# Schematic.net
KiCad netlist of a schematic drawn in Altium Designer
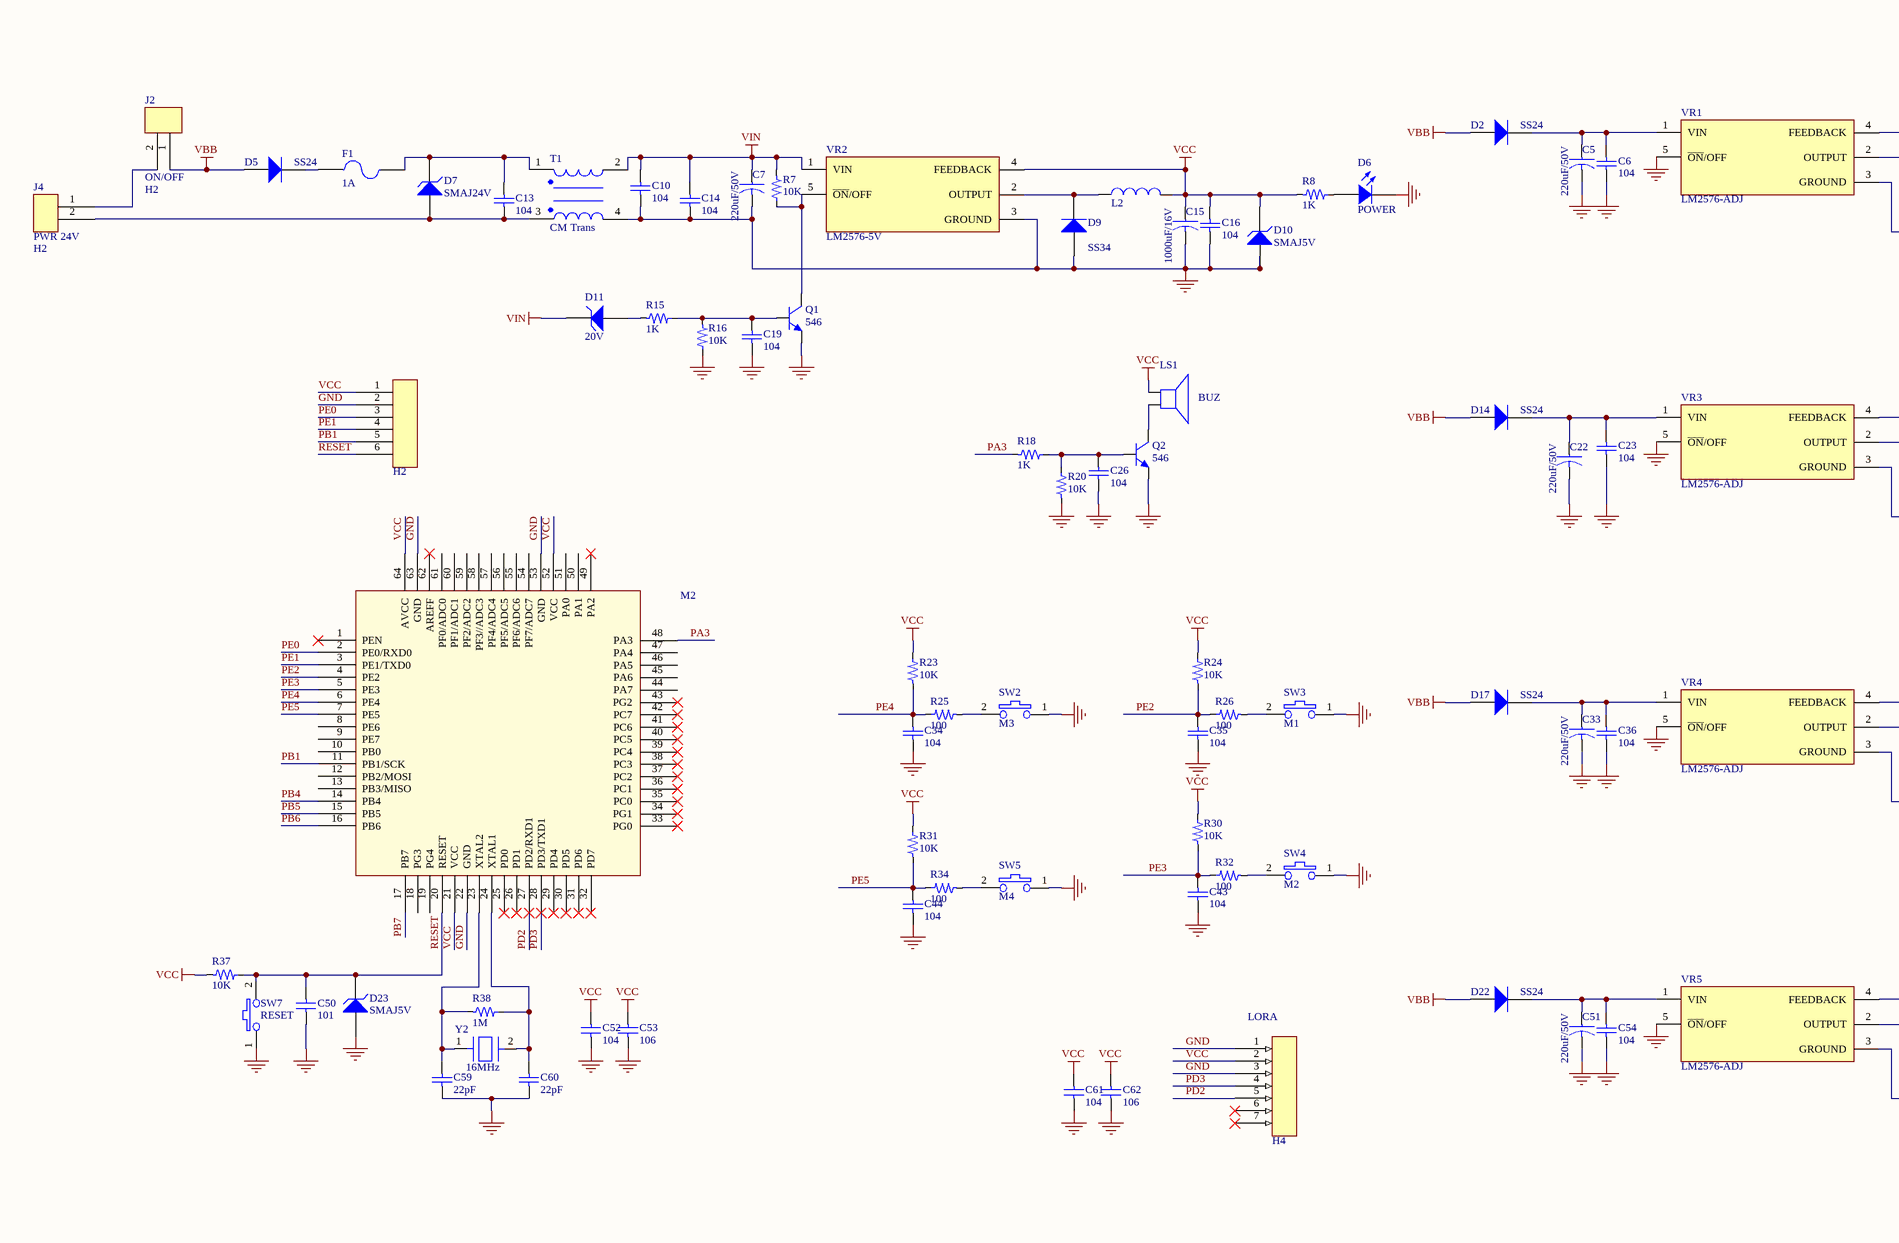
[diagram p0: Schematic.SchDoc, left]
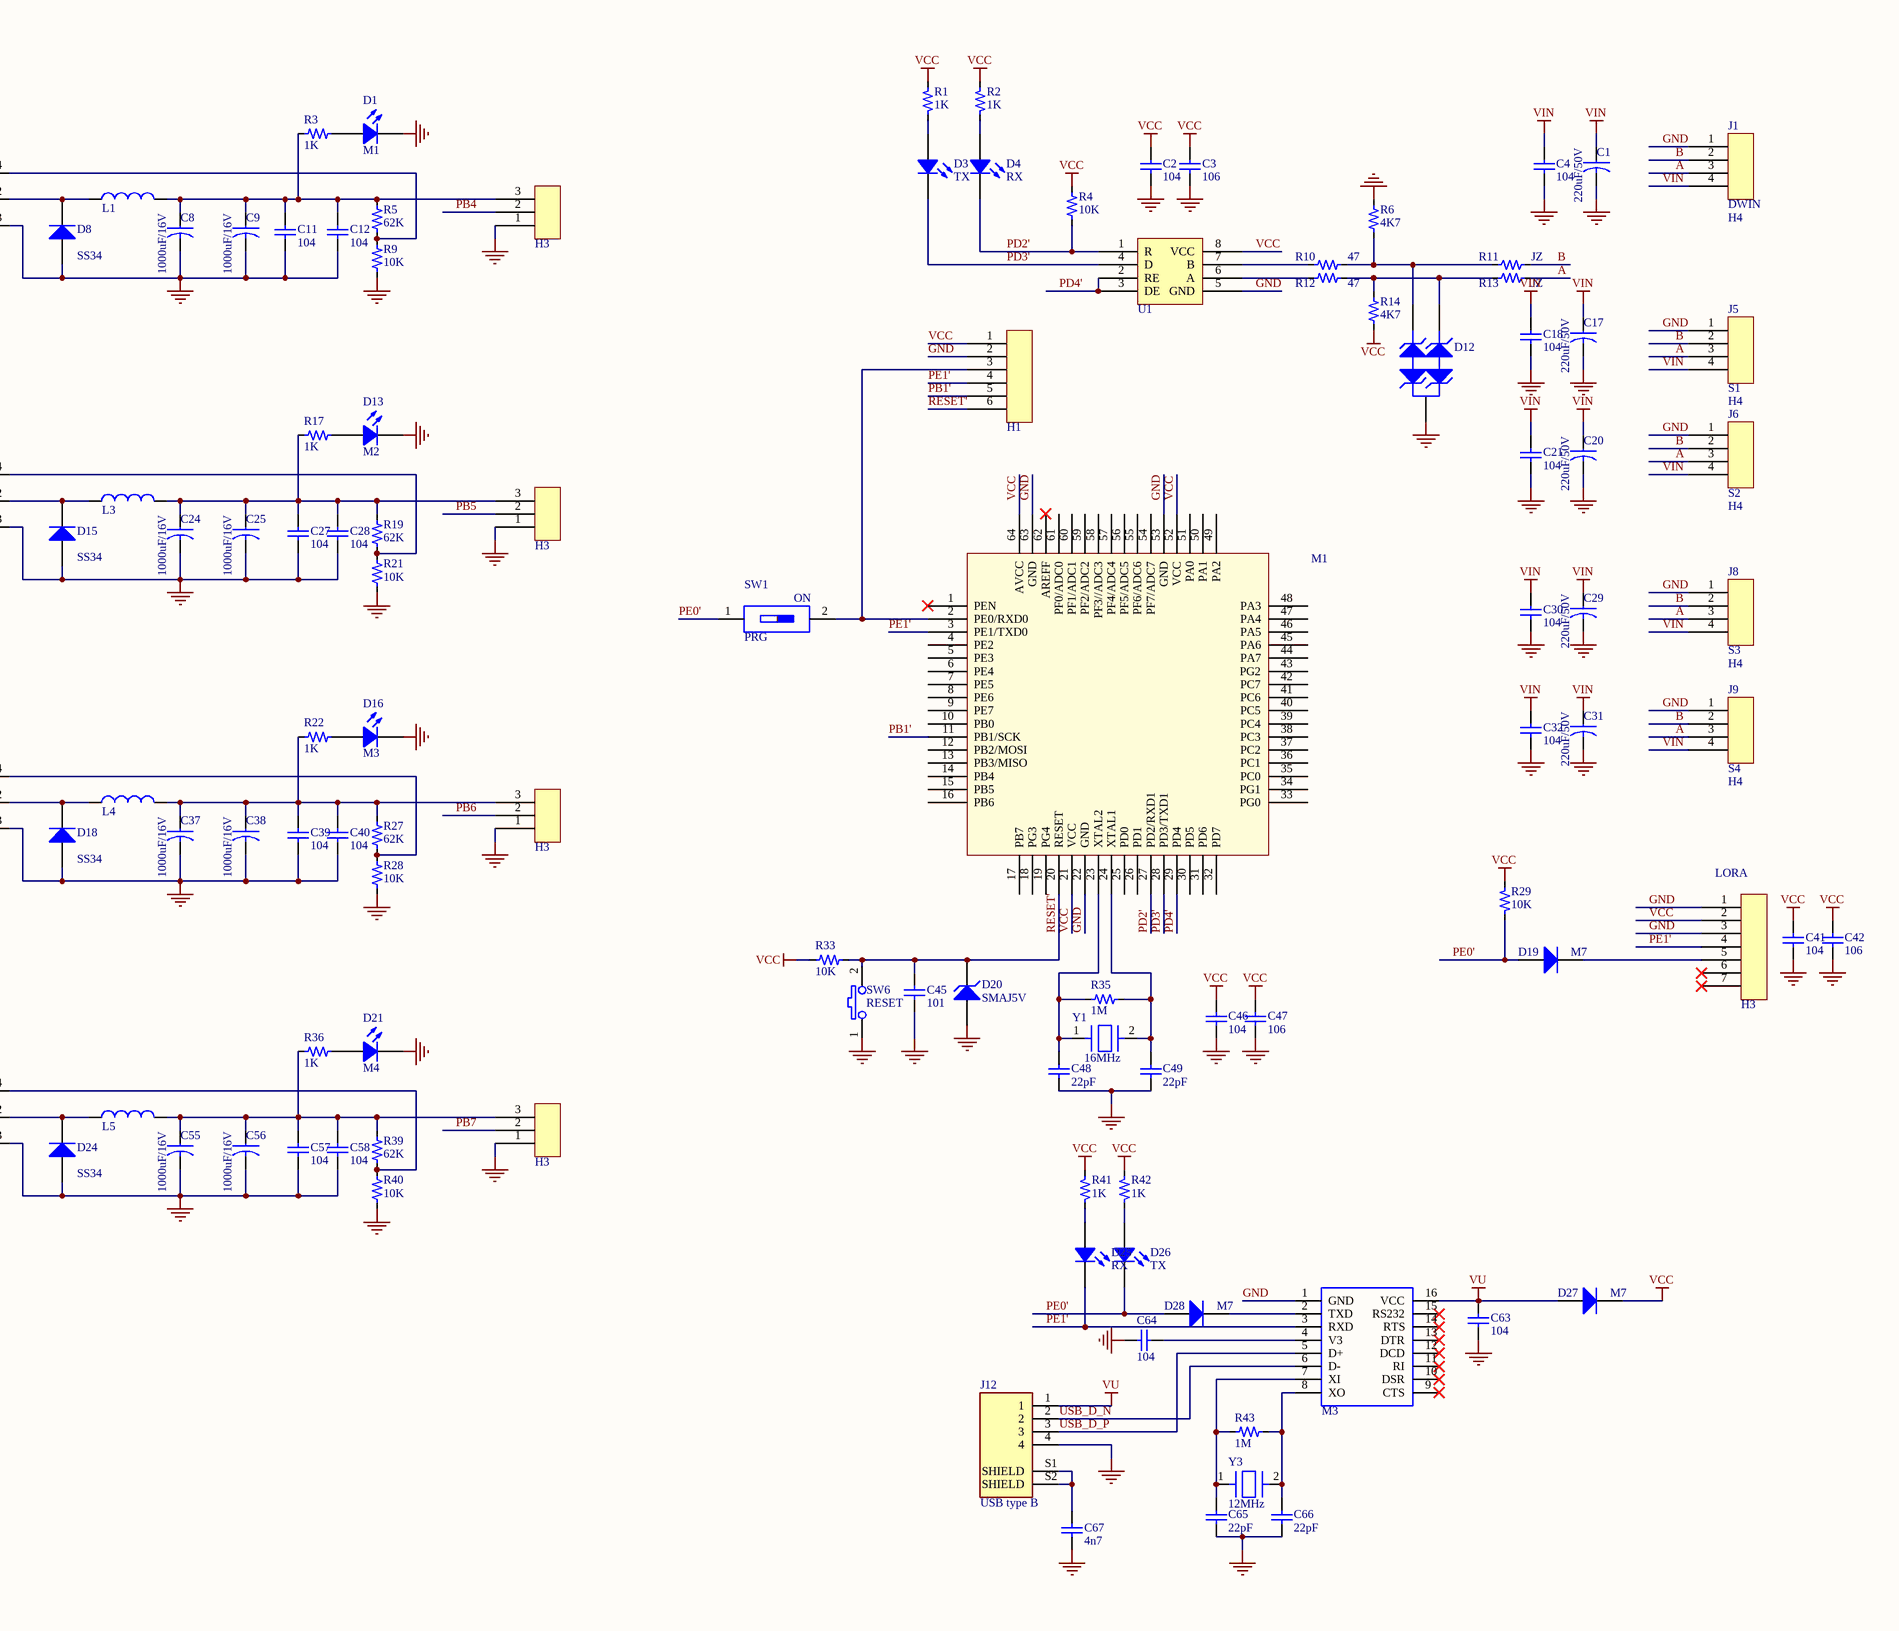
[diagram p1: Schematic.SchDoc, right]

(export (version "E")
  (design (tool "Eeschema 10.0.6"))
  (components
    (comp (ref "C1")
      (value "220uF/50V")
      (footprint "CAP-P-1W")
      (fields
        (field (name "MP") "EEE-FK1H221GP")
        (field (name "MF") "Panasonic Electronic")
        (field (name "Comment") "CAP POL")
      )
      (libsource (lib "Discrete") (part "CAP POL"))
    )
    (comp (ref "C2")
      (value "104")
      (footprint "C-1206")
      (description "Capacitor")
      (fields (field (name "Comment") "Cap") (field (name "PUBLISHER") "Altium Limited"))
      (libsource (lib "Discrete") (part "Cap"))
    )
    (comp (ref "C3")
      (value "106")
      (footprint "C-1206")
      (description "Capacitor")
      (fields (field (name "Comment") "Cap") (field (name "PUBLISHER") "Altium Limited"))
      (libsource (lib "Discrete") (part "Cap"))
    )
    (comp (ref "C4")
      (value "104")
      (footprint "C-1206")
      (description "Capacitor")
      (fields (field (name "Comment") "Cap") (field (name "PUBLISHER") "Altium Limited"))
      (libsource (lib "Discrete") (part "Cap"))
    )
    (comp (ref "C5")
      (value "220uF/50V")
      (footprint "CAP-P-1W")
      (fields
        (field (name "MP") "EEE-FK1H221GP")
        (field (name "MF") "Panasonic Electronic")
        (field (name "Comment") "CAP POL")
      )
      (libsource (lib "Discrete") (part "CAP POL"))
    )
    (comp (ref "C6")
      (value "104")
      (footprint "C-1206")
      (description "Capacitor")
      (fields (field (name "Comment") "Cap") (field (name "PUBLISHER") "Altium Limited"))
      (libsource (lib "Discrete") (part "Cap"))
    )
    (comp (ref "C7")
      (value "220uF/50V")
      (footprint "CAP-P-1W")
      (fields
        (field (name "MP") "EEE-FK1H221GP")
        (field (name "MF") "Panasonic Electronic")
        (field (name "Comment") "CAP POL")
      )
      (libsource (lib "Discrete") (part "CAP POL"))
    )
    (comp (ref "C8")
      (value "1000uF/16V")
      (footprint "CAP-P-2")
      (fields
        (field (name "MP") "EEE-FK1H221GP")
        (field (name "MF") "Panasonic Electronic")
        (field (name "Comment") "CAP POL")
      )
      (libsource (lib "Discrete") (part "CAP POL"))
    )
    (comp (ref "C9")
      (value "1000uF/16V")
      (footprint "CAP-P-2")
      (fields
        (field (name "MP") "EEE-FK1H221GP")
        (field (name "MF") "Panasonic Electronic")
        (field (name "Comment") "CAP POL")
      )
      (libsource (lib "Discrete") (part "CAP POL"))
    )
    (comp (ref "C10")
      (value "104")
      (footprint "CAP-NP-1")
      (description "Capacitor")
      (fields (field (name "Comment") "Cap") (field (name "PUBLISHER") "Altium Limited"))
      (libsource (lib "Discrete") (part "Cap"))
    )
    (comp (ref "C11")
      (value "104")
      (footprint "C-1206")
      (description "Capacitor")
      (fields (field (name "Comment") "Cap") (field (name "PUBLISHER") "Altium Limited"))
      (libsource (lib "Discrete") (part "Cap"))
    )
    (comp (ref "C12")
      (value "104")
      (footprint "C-1206")
      (description "Capacitor")
      (fields (field (name "Comment") "Cap") (field (name "PUBLISHER") "Altium Limited"))
      (libsource (lib "Discrete") (part "Cap"))
    )
    (comp (ref "C13")
      (value "104")
      (footprint "CAP-NP-1")
      (description "Capacitor")
      (fields (field (name "Comment") "Cap") (field (name "PUBLISHER") "Altium Limited"))
      (libsource (lib "Discrete") (part "Cap"))
    )
    (comp (ref "C14")
      (value "104")
      (footprint "C-1206")
      (description "Capacitor")
      (fields (field (name "Comment") "Cap") (field (name "PUBLISHER") "Altium Limited"))
      (libsource (lib "Discrete") (part "Cap"))
    )
    (comp (ref "C15")
      (value "1000uF/16V")
      (footprint "CAP-P-2")
      (fields
        (field (name "MP") "EEE-FK1H221GP")
        (field (name "MF") "Panasonic Electronic")
        (field (name "Comment") "CAP POL")
      )
      (libsource (lib "Discrete") (part "CAP POL"))
    )
    (comp (ref "C16")
      (value "104")
      (footprint "C-1206")
      (description "Capacitor")
      (fields (field (name "Comment") "Cap") (field (name "PUBLISHER") "Altium Limited"))
      (libsource (lib "Discrete") (part "Cap"))
    )
    (comp (ref "C17")
      (value "220uF/50V")
      (footprint "CAP-P-1W")
      (fields
        (field (name "MP") "EEE-FK1H221GP")
        (field (name "MF") "Panasonic Electronic")
        (field (name "Comment") "CAP POL")
      )
      (libsource (lib "Discrete") (part "CAP POL"))
    )
    (comp (ref "C18")
      (value "104")
      (footprint "C-1206")
      (description "Capacitor")
      (fields (field (name "Comment") "Cap") (field (name "PUBLISHER") "Altium Limited"))
      (libsource (lib "Discrete") (part "Cap"))
    )
    (comp (ref "C19")
      (value "104")
      (footprint "C-1206")
      (description "Capacitor")
      (fields (field (name "Comment") "Cap") (field (name "PUBLISHER") "Altium Limited"))
      (libsource (lib "Discrete") (part "Cap"))
    )
    (comp (ref "C20")
      (value "220uF/50V")
      (footprint "CAP-P-1W")
      (fields
        (field (name "MP") "EEE-FK1H221GP")
        (field (name "MF") "Panasonic Electronic")
        (field (name "Comment") "CAP POL")
      )
      (libsource (lib "Discrete") (part "CAP POL"))
    )
    (comp (ref "C21")
      (value "104")
      (footprint "C-1206")
      (description "Capacitor")
      (fields (field (name "Comment") "Cap") (field (name "PUBLISHER") "Altium Limited"))
      (libsource (lib "Discrete") (part "Cap"))
    )
    (comp (ref "C22")
      (value "220uF/50V")
      (footprint "CAP-P-1W")
      (fields
        (field (name "MP") "EEE-FK1H221GP")
        (field (name "MF") "Panasonic Electronic")
        (field (name "Comment") "CAP POL")
      )
      (libsource (lib "Discrete") (part "CAP POL"))
    )
    (comp (ref "C23")
      (value "104")
      (footprint "C-1206")
      (description "Capacitor")
      (fields (field (name "Comment") "Cap") (field (name "PUBLISHER") "Altium Limited"))
      (libsource (lib "Discrete") (part "Cap"))
    )
    (comp (ref "C24")
      (value "1000uF/16V")
      (footprint "CAP-P-2")
      (fields
        (field (name "MP") "EEE-FK1H221GP")
        (field (name "MF") "Panasonic Electronic")
        (field (name "Comment") "CAP POL")
      )
      (libsource (lib "Discrete") (part "CAP POL"))
    )
    (comp (ref "C25")
      (value "1000uF/16V")
      (footprint "CAP-P-2")
      (fields
        (field (name "MP") "EEE-FK1H221GP")
        (field (name "MF") "Panasonic Electronic")
        (field (name "Comment") "CAP POL")
      )
      (libsource (lib "Discrete") (part "CAP POL"))
    )
    (comp (ref "C26")
      (value "104")
      (footprint "C-1206")
      (description "Capacitor")
      (fields (field (name "Comment") "Cap") (field (name "PUBLISHER") "Altium Limited"))
      (libsource (lib "Discrete") (part "Cap"))
    )
    (comp (ref "C27")
      (value "104")
      (footprint "C-1206")
      (description "Capacitor")
      (fields (field (name "Comment") "Cap") (field (name "PUBLISHER") "Altium Limited"))
      (libsource (lib "Discrete") (part "Cap"))
    )
    (comp (ref "C28")
      (value "104")
      (footprint "C-1206")
      (description "Capacitor")
      (fields (field (name "Comment") "Cap") (field (name "PUBLISHER") "Altium Limited"))
      (libsource (lib "Discrete") (part "Cap"))
    )
    (comp (ref "C29")
      (value "220uF/50V")
      (footprint "CAP-P-1W")
      (fields
        (field (name "MP") "EEE-FK1H221GP")
        (field (name "MF") "Panasonic Electronic")
        (field (name "Comment") "CAP POL")
      )
      (libsource (lib "Discrete") (part "CAP POL"))
    )
    (comp (ref "C30")
      (value "104")
      (footprint "C-1206")
      (description "Capacitor")
      (fields (field (name "Comment") "Cap") (field (name "PUBLISHER") "Altium Limited"))
      (libsource (lib "Discrete") (part "Cap"))
    )
    (comp (ref "C31")
      (value "220uF/50V")
      (footprint "CAP-P-1W")
      (fields
        (field (name "MP") "EEE-FK1H221GP")
        (field (name "MF") "Panasonic Electronic")
        (field (name "Comment") "CAP POL")
      )
      (libsource (lib "Discrete") (part "CAP POL"))
    )
    (comp (ref "C32")
      (value "104")
      (footprint "C-1206")
      (description "Capacitor")
      (fields (field (name "Comment") "Cap") (field (name "PUBLISHER") "Altium Limited"))
      (libsource (lib "Discrete") (part "Cap"))
    )
    (comp (ref "C33")
      (value "220uF/50V")
      (footprint "CAP-P-1W")
      (fields
        (field (name "MP") "EEE-FK1H221GP")
        (field (name "MF") "Panasonic Electronic")
        (field (name "Comment") "CAP POL")
      )
      (libsource (lib "Discrete") (part "CAP POL"))
    )
    (comp (ref "C34")
      (value "104")
      (footprint "C-1206")
      (description "Capacitor")
      (fields (field (name "Comment") "Cap") (field (name "PUBLISHER") "Altium Limited"))
      (libsource (lib "Discrete") (part "Cap"))
    )
    (comp (ref "C35")
      (value "104")
      (footprint "C-1206")
      (description "Capacitor")
      (fields (field (name "Comment") "Cap") (field (name "PUBLISHER") "Altium Limited"))
      (libsource (lib "Discrete") (part "Cap"))
    )
    (comp (ref "C36")
      (value "104")
      (footprint "C-1206")
      (description "Capacitor")
      (fields (field (name "Comment") "Cap") (field (name "PUBLISHER") "Altium Limited"))
      (libsource (lib "Discrete") (part "Cap"))
    )
    (comp (ref "C37")
      (value "1000uF/16V")
      (footprint "CAP-P-2")
      (fields
        (field (name "MP") "EEE-FK1H221GP")
        (field (name "MF") "Panasonic Electronic")
        (field (name "Comment") "CAP POL")
      )
      (libsource (lib "Discrete") (part "CAP POL"))
    )
    (comp (ref "C38")
      (value "1000uF/16V")
      (footprint "CAP-P-2")
      (fields
        (field (name "MP") "EEE-FK1H221GP")
        (field (name "MF") "Panasonic Electronic")
        (field (name "Comment") "CAP POL")
      )
      (libsource (lib "Discrete") (part "CAP POL"))
    )
    (comp (ref "C39")
      (value "104")
      (footprint "C-1206")
      (description "Capacitor")
      (fields (field (name "Comment") "Cap") (field (name "PUBLISHER") "Altium Limited"))
      (libsource (lib "Discrete") (part "Cap"))
    )
    (comp (ref "C40")
      (value "104")
      (footprint "C-1206")
      (description "Capacitor")
      (fields (field (name "Comment") "Cap") (field (name "PUBLISHER") "Altium Limited"))
      (libsource (lib "Discrete") (part "Cap"))
    )
    (comp (ref "C41")
      (value "104")
      (footprint "C-1206")
      (description "Capacitor")
      (fields (field (name "Comment") "Cap") (field (name "PUBLISHER") "Altium Limited"))
      (libsource (lib "Discrete") (part "Cap"))
    )
    (comp (ref "C42")
      (value "106")
      (footprint "C-1206")
      (description "Capacitor")
      (fields (field (name "Comment") "Cap") (field (name "PUBLISHER") "Altium Limited"))
      (libsource (lib "Discrete") (part "Cap"))
    )
    (comp (ref "C43")
      (value "104")
      (footprint "C-1206")
      (description "Capacitor")
      (fields (field (name "Comment") "Cap") (field (name "PUBLISHER") "Altium Limited"))
      (libsource (lib "Discrete") (part "Cap"))
    )
    (comp (ref "C44")
      (value "104")
      (footprint "C-1206")
      (description "Capacitor")
      (fields (field (name "Comment") "Cap") (field (name "PUBLISHER") "Altium Limited"))
      (libsource (lib "Discrete") (part "Cap"))
    )
    (comp (ref "C45")
      (value "101")
      (footprint "C-1206")
      (description "Capacitor")
      (fields (field (name "Comment") "Cap") (field (name "PUBLISHER") "Altium Limited"))
      (libsource (lib "Discrete") (part "Cap"))
    )
    (comp (ref "C46")
      (value "104")
      (footprint "C-1206")
      (description "Capacitor")
      (fields (field (name "Comment") "Cap") (field (name "PUBLISHER") "Altium Limited"))
      (libsource (lib "Discrete") (part "Cap"))
    )
    (comp (ref "C47")
      (value "106")
      (footprint "C-1206")
      (description "Capacitor")
      (fields (field (name "Comment") "Cap") (field (name "PUBLISHER") "Altium Limited"))
      (libsource (lib "Discrete") (part "Cap"))
    )
    (comp (ref "C48")
      (value "22pF")
      (footprint "C-1206")
      (description "Capacitor")
      (fields (field (name "Comment") "Cap") (field (name "PUBLISHER") "Altium Limited"))
      (libsource (lib "Discrete") (part "Cap"))
    )
    (comp (ref "C49")
      (value "22pF")
      (footprint "C-1206")
      (description "Capacitor")
      (fields (field (name "Comment") "Cap") (field (name "PUBLISHER") "Altium Limited"))
      (libsource (lib "Discrete") (part "Cap"))
    )
    (comp (ref "C50")
      (value "101")
      (footprint "C-1206")
      (description "Capacitor")
      (fields (field (name "Comment") "Cap") (field (name "PUBLISHER") "Altium Limited"))
      (libsource (lib "Discrete") (part "Cap"))
    )
    (comp (ref "C51")
      (value "220uF/50V")
      (footprint "CAP-P-1W")
      (fields
        (field (name "MP") "EEE-FK1H221GP")
        (field (name "MF") "Panasonic Electronic")
        (field (name "Comment") "CAP POL")
      )
      (libsource (lib "Discrete") (part "CAP POL"))
    )
    (comp (ref "C52")
      (value "104")
      (footprint "C-1206")
      (description "Capacitor")
      (fields (field (name "Comment") "Cap") (field (name "PUBLISHER") "Altium Limited"))
      (libsource (lib "Discrete") (part "Cap"))
    )
    (comp (ref "C53")
      (value "106")
      (footprint "C-1206")
      (description "Capacitor")
      (fields (field (name "Comment") "Cap") (field (name "PUBLISHER") "Altium Limited"))
      (libsource (lib "Discrete") (part "Cap"))
    )
    (comp (ref "C54")
      (value "104")
      (footprint "C-1206")
      (description "Capacitor")
      (fields (field (name "Comment") "Cap") (field (name "PUBLISHER") "Altium Limited"))
      (libsource (lib "Discrete") (part "Cap"))
    )
    (comp (ref "C55")
      (value "1000uF/16V")
      (footprint "CAP-P-2")
      (fields
        (field (name "MP") "EEE-FK1H221GP")
        (field (name "MF") "Panasonic Electronic")
        (field (name "Comment") "CAP POL")
      )
      (libsource (lib "Discrete") (part "CAP POL"))
    )
    (comp (ref "C56")
      (value "1000uF/16V")
      (footprint "CAP-P-2")
      (fields
        (field (name "MP") "EEE-FK1H221GP")
        (field (name "MF") "Panasonic Electronic")
        (field (name "Comment") "CAP POL")
      )
      (libsource (lib "Discrete") (part "CAP POL"))
    )
    (comp (ref "C57")
      (value "104")
      (footprint "C-1206")
      (description "Capacitor")
      (fields (field (name "Comment") "Cap") (field (name "PUBLISHER") "Altium Limited"))
      (libsource (lib "Discrete") (part "Cap"))
    )
    (comp (ref "C58")
      (value "104")
      (footprint "C-1206")
      (description "Capacitor")
      (fields (field (name "Comment") "Cap") (field (name "PUBLISHER") "Altium Limited"))
      (libsource (lib "Discrete") (part "Cap"))
    )
    (comp (ref "C59")
      (value "22pF")
      (footprint "C-1206")
      (description "Capacitor")
      (fields (field (name "Comment") "Cap") (field (name "PUBLISHER") "Altium Limited"))
      (libsource (lib "Discrete") (part "Cap"))
    )
    (comp (ref "C60")
      (value "22pF")
      (footprint "C-1206")
      (description "Capacitor")
      (fields (field (name "Comment") "Cap") (field (name "PUBLISHER") "Altium Limited"))
      (libsource (lib "Discrete") (part "Cap"))
    )
    (comp (ref "C61")
      (value "104")
      (footprint "C-1206")
      (description "Capacitor")
      (fields (field (name "Comment") "Cap") (field (name "PUBLISHER") "Altium Limited"))
      (libsource (lib "Discrete") (part "Cap"))
    )
    (comp (ref "C62")
      (value "106")
      (footprint "C-1206")
      (description "Capacitor")
      (fields (field (name "Comment") "Cap") (field (name "PUBLISHER") "Altium Limited"))
      (libsource (lib "Discrete") (part "Cap"))
    )
    (comp (ref "C63")
      (value "104")
      (footprint "C-1206")
      (description "Capacitor")
      (fields (field (name "Comment") "Cap") (field (name "PUBLISHER") "Altium Limited"))
      (libsource (lib "Discrete") (part "Cap"))
    )
    (comp (ref "C64")
      (value "104")
      (footprint "C-1206")
      (description "Capacitor")
      (fields (field (name "Comment") "Cap") (field (name "PUBLISHER") "Altium Limited"))
      (libsource (lib "Discrete") (part "Cap"))
    )
    (comp (ref "C65")
      (value "22pF")
      (footprint "C-1206")
      (description "Capacitor")
      (fields (field (name "Comment") "Cap") (field (name "PUBLISHER") "Altium Limited"))
      (libsource (lib "Discrete") (part "Cap"))
    )
    (comp (ref "C66")
      (value "22pF")
      (footprint "C-1206")
      (description "Capacitor")
      (fields (field (name "Comment") "Cap") (field (name "PUBLISHER") "Altium Limited"))
      (libsource (lib "Discrete") (part "Cap"))
    )
    (comp (ref "C67")
      (value "4n7")
      (footprint "C-1206")
      (description "Capacitor")
      (fields (field (name "Comment") "Cap") (field (name "PUBLISHER") "Altium Limited"))
      (libsource (lib "Discrete") (part "Cap"))
    )
    (comp (ref "D1")
      (value "M1")
      (footprint "L-1206")
      (description "Typical INFRARED GaAs LED")
      (fields (field (name "Comment") "PWR") (field (name "PUBLISHER") "Altium Limited"))
      (libsource (lib "Discrete") (part "LED"))
    )
    (comp (ref "D2")
      (value "SS24")
      (footprint "SMB")
      (description "Default Diode")
      (fields (field (name "Comment") "Diode") (field (name "PUBLISHER") "Altium Limited"))
      (libsource (lib "Discrete") (part "Diode"))
    )
    (comp (ref "D3")
      (value "TX")
      (footprint "L-1206")
      (description "Typical INFRARED GaAs LED")
      (fields (field (name "PUBLISHER") "Altium Limited"))
      (libsource (lib "Discrete") (part "LED"))
    )
    (comp (ref "D4")
      (value "RX")
      (footprint "L-1206")
      (description "Typical INFRARED GaAs LED")
      (fields (field (name "PUBLISHER") "Altium Limited"))
      (libsource (lib "Discrete") (part "LED"))
    )
    (comp (ref "D5")
      (value "SS24")
      (footprint "SMB")
      (description "Default Diode")
      (fields (field (name "Comment") "Diode") (field (name "PUBLISHER") "Altium Limited"))
      (libsource (lib "Discrete") (part "Diode"))
    )
    (comp (ref "D6")
      (value "POWER")
      (footprint "L-1206")
      (description "Typical INFRARED GaAs LED")
      (fields (field (name "Comment") "PWR") (field (name "PUBLISHER") "Altium Limited"))
      (libsource (lib "Discrete") (part "LED"))
    )
    (comp (ref "D7")
      (value "SMAJ24V")
      (footprint "SMA")
      (fields
        (field (name "MP") "SMBJ24CA")
        (field (name "MF") "Taiwan Semiconductor")
        (field (name "Comment") "Zener Diode")
      )
      (libsource (lib "Discrete") (part "Zener Diode"))
    )
    (comp (ref "D8")
      (value "SS34")
      (footprint "SMA")
      (description "Default Diode")
      (fields (field (name "Comment") "Diode") (field (name "PUBLISHER") "Altium Limited"))
      (libsource (lib "Discrete") (part "Diode"))
    )
    (comp (ref "D9")
      (value "SS34")
      (footprint "SMA")
      (description "Default Diode")
      (fields (field (name "Comment") "Diode") (field (name "PUBLISHER") "Altium Limited"))
      (libsource (lib "Discrete") (part "Diode"))
    )
    (comp (ref "D10")
      (value "SMAJ5V")
      (footprint "SMA")
      (fields
        (field (name "MP") "SMBJ24CA")
        (field (name "MF") "Taiwan Semiconductor")
        (field (name "Comment") "Zener Diode")
      )
      (libsource (lib "Discrete") (part "Zener Diode"))
    )
    (comp (ref "D11")
      (value "20V")
      (footprint "ZDiode-3")
      (fields
        (field (name "MP") "SMBJ24CA")
        (field (name "MF") "Taiwan Semiconductor")
        (field (name "Comment") "Zener Diode")
      )
      (libsource (lib "Discrete") (part "Zener Diode"))
    )
    (comp (ref "D12") (value "PSM712") (footprint "SOT23") (libsource (lib "Discrete") (part "PSM712")))
    (comp (ref "D13")
      (value "M2")
      (footprint "L-1206")
      (description "Typical INFRARED GaAs LED")
      (fields (field (name "Comment") "PWR") (field (name "PUBLISHER") "Altium Limited"))
      (libsource (lib "Discrete") (part "LED"))
    )
    (comp (ref "D14")
      (value "SS24")
      (footprint "SMB")
      (description "Default Diode")
      (fields (field (name "Comment") "Diode") (field (name "PUBLISHER") "Altium Limited"))
      (libsource (lib "Discrete") (part "Diode"))
    )
    (comp (ref "D15")
      (value "SS34")
      (footprint "SMA")
      (description "Default Diode")
      (fields (field (name "Comment") "Diode") (field (name "PUBLISHER") "Altium Limited"))
      (libsource (lib "Discrete") (part "Diode"))
    )
    (comp (ref "D16")
      (value "M3")
      (footprint "L-1206")
      (description "Typical INFRARED GaAs LED")
      (fields (field (name "Comment") "PWR") (field (name "PUBLISHER") "Altium Limited"))
      (libsource (lib "Discrete") (part "LED"))
    )
    (comp (ref "D17")
      (value "SS24")
      (footprint "SMB")
      (description "Default Diode")
      (fields (field (name "Comment") "Diode") (field (name "PUBLISHER") "Altium Limited"))
      (libsource (lib "Discrete") (part "Diode"))
    )
    (comp (ref "D18")
      (value "SS34")
      (footprint "SMA")
      (description "Default Diode")
      (fields (field (name "Comment") "Diode") (field (name "PUBLISHER") "Altium Limited"))
      (libsource (lib "Discrete") (part "Diode"))
    )
    (comp (ref "D19")
      (value "M7")
      (footprint "SMA")
      (description "Default Diode")
      (fields (field (name "Comment") "Diode") (field (name "PUBLISHER") "Altium Limited"))
      (libsource (lib "Discrete") (part "Diode"))
    )
    (comp (ref "D20")
      (value "SMAJ5V")
      (footprint "SMA")
      (fields
        (field (name "MP") "SMBJ24CA")
        (field (name "MF") "Taiwan Semiconductor")
        (field (name "Comment") "Zener Diode")
      )
      (libsource (lib "Discrete") (part "Zener Diode"))
    )
    (comp (ref "D21")
      (value "M4")
      (footprint "L-1206")
      (description "Typical INFRARED GaAs LED")
      (fields (field (name "Comment") "PWR") (field (name "PUBLISHER") "Altium Limited"))
      (libsource (lib "Discrete") (part "LED"))
    )
    (comp (ref "D22")
      (value "SS24")
      (footprint "SMB")
      (description "Default Diode")
      (fields (field (name "Comment") "Diode") (field (name "PUBLISHER") "Altium Limited"))
      (libsource (lib "Discrete") (part "Diode"))
    )
    (comp (ref "D23")
      (value "SMAJ5V")
      (footprint "SMA")
      (fields
        (field (name "MP") "SMBJ24CA")
        (field (name "MF") "Taiwan Semiconductor")
        (field (name "Comment") "Zener Diode")
      )
      (libsource (lib "Discrete") (part "Zener Diode"))
    )
    (comp (ref "D24")
      (value "SS34")
      (footprint "SMA")
      (description "Default Diode")
      (fields (field (name "Comment") "Diode") (field (name "PUBLISHER") "Altium Limited"))
      (libsource (lib "Discrete") (part "Diode"))
    )
    (comp (ref "D25")
      (value "RX")
      (footprint "L-1206")
      (description "Typical INFRARED GaAs LED")
      (fields (field (name "PUBLISHER") "Altium Limited"))
      (libsource (lib "Discrete") (part "LED"))
    )
    (comp (ref "D26")
      (value "TX")
      (footprint "L-1206")
      (description "Typical INFRARED GaAs LED")
      (fields (field (name "PUBLISHER") "Altium Limited"))
      (libsource (lib "Discrete") (part "LED"))
    )
    (comp (ref "D27")
      (value "M7")
      (footprint "SMA")
      (description "Default Diode")
      (fields (field (name "Comment") "Diode") (field (name "PUBLISHER") "Altium Limited"))
      (libsource (lib "Discrete") (part "Diode"))
    )
    (comp (ref "D28")
      (value "M7")
      (footprint "SMA")
      (description "Default Diode")
      (fields (field (name "Comment") "Diode") (field (name "PUBLISHER") "Altium Limited"))
      (libsource (lib "Discrete") (part "Diode"))
    )
    (comp (ref "F1")
      (value "1A")
      (footprint "FUSE")
      (description "Fuse")
      (fields (field (name "PUBLISHER") "Altium Limited"))
      (libsource (lib "Discrete") (part "Fuse"))
    )
    (comp (ref "H1") (value "H_1X6") (footprint "Header-01X06") (libsource (lib "Headers") (part "H_1X6")))
    (comp (ref "H2") (value "H_1X6") (footprint "Header-01X06") (libsource (lib "Headers") (part "H_1X6")))
    (comp (ref "H3") (value "LORA") (footprint "Header-01X07") (libsource (lib "Headers") (part "H_1X7")))
    (comp (ref "H4") (value "LORA") (footprint "Header-01X07") (libsource (lib "Headers") (part "H_1X7")))
    (comp (ref "J1")
      (value "DWIN")
      (footprint "STD-04-3.55MM")
      (fields (field (name "ALTIUM_VALUE") "H4"))
      (libsource (lib "Connectors") (part "CON04"))
    )
    (comp (ref "J2")
      (value "ON/OFF")
      (footprint "PLG-02-B")
      (fields (field (name "ALTIUM_VALUE") "H2"))
      (libsource (lib "Connectors") (part "CON02"))
    )
    (comp (ref "J3")
      (value "H3")
      (footprint "PLG-03-B")
      (fields (field (name "Comment") "MOTOR1"))
      (libsource (lib "Connectors") (part "CON03"))
    )
    (comp (ref "J4")
      (value "PWR 24V")
      (footprint "PLG-02-B")
      (fields (field (name "ALTIUM_VALUE") "H2"))
      (libsource (lib "") (part "CON02_1"))
    )
    (comp (ref "J5")
      (value "S1")
      (footprint "STD-04-3.55MM")
      (fields (field (name "ALTIUM_VALUE") "H4"))
      (libsource (lib "Connectors") (part "CON04"))
    )
    (comp (ref "J6")
      (value "S2")
      (footprint "STD-04-3.55MM")
      (fields (field (name "ALTIUM_VALUE") "H4"))
      (libsource (lib "Connectors") (part "CON04"))
    )
    (comp (ref "J7")
      (value "H3")
      (footprint "PLG-03-B")
      (fields (field (name "Comment") "MOTOR2"))
      (libsource (lib "Connectors") (part "CON03"))
    )
    (comp (ref "J8")
      (value "S3")
      (footprint "STD-04-3.55MM")
      (fields (field (name "ALTIUM_VALUE") "H4"))
      (libsource (lib "Connectors") (part "CON04"))
    )
    (comp (ref "J9")
      (value "S4")
      (footprint "STD-04-3.55MM")
      (fields (field (name "ALTIUM_VALUE") "H4"))
      (libsource (lib "Connectors") (part "CON04"))
    )
    (comp (ref "J10")
      (value "H3")
      (footprint "PLG-03-B")
      (fields (field (name "Comment") "MOTOR3"))
      (libsource (lib "Connectors") (part "CON03"))
    )
    (comp (ref "J11")
      (value "H3")
      (footprint "PLG-03-B")
      (fields (field (name "Comment") "MOTOR4"))
      (libsource (lib "Connectors") (part "CON03"))
    )
    (comp (ref "J12")
      (value "USB type B")
      (footprint "USB-Type-B")
      (description "USB-B (USB TYPE-B) USB 2.0 Receptacle Connector 4 Position Through Hole, Right Angle")
      (fields (field (name "MF") "Wurth Elektronik") (field (name "MP") "61400416121"))
      (libsource (lib "Sockets") (part "USB type B"))
    )
    (comp (ref "L1")
      (value "Inductor")
      (footprint "L_9X12")
      (fields (field (name "PUBLISHER") "Altium Limited"))
      (libsource (lib "Discrete") (part "Inductor"))
    )
    (comp (ref "L2")
      (value "Inductor")
      (footprint "L_9X12")
      (fields (field (name "PUBLISHER") "Altium Limited"))
      (libsource (lib "Discrete") (part "Inductor"))
    )
    (comp (ref "L3")
      (value "Inductor")
      (footprint "L_9X12")
      (fields (field (name "PUBLISHER") "Altium Limited"))
      (libsource (lib "Discrete") (part "Inductor"))
    )
    (comp (ref "L4")
      (value "Inductor")
      (footprint "L_9X12")
      (fields (field (name "PUBLISHER") "Altium Limited"))
      (libsource (lib "Discrete") (part "Inductor"))
    )
    (comp (ref "L5")
      (value "Inductor")
      (footprint "L_9X12")
      (fields (field (name "PUBLISHER") "Altium Limited"))
      (libsource (lib "Discrete") (part "Inductor"))
    )
    (comp (ref "LS1")
      (value "BUZ")
      (footprint "Buzzer")
      (fields
        (field (name "MF") "PUI Audio, Inc.")
        (field (name "MP") "AI-1027-TWT-3V-R")
        (field (name "Comment") "Buzzer")
      )
      (libsource (lib "Discrete") (part "Buzzer"))
    )
    (comp (ref "M1")
      (value "Atmega128-SMD")
      (footprint "Quad64")
      (libsource (lib "Microcontrollers") (part "Atmega128-SMD"))
    )
    (comp (ref "M2")
      (value "Atmega128-SMD")
      (footprint "Quad64")
      (libsource (lib "Microcontrollers") (part "Atmega128-SMD"))
    )
    (comp (ref "M3") (value "CH340") (footprint "SOIC-16") (libsource (lib "Misc") (part "CH340")))
    (comp (ref "Q1")
      (value "546")
      (footprint "SOT23")
      (description "NPN Bipolar Transistor")
      (fields (field (name "Comment") "NPN") (field (name "PUBLISHER") "Altium Limited"))
      (libsource (lib "Discrete") (part "NPN-CBE"))
    )
    (comp (ref "Q2")
      (value "546")
      (footprint "SOT23")
      (description "NPN Bipolar Transistor")
      (fields (field (name "Comment") "NPN") (field (name "PUBLISHER") "Altium Limited"))
      (libsource (lib "Discrete") (part "NPN-CBE"))
    )
    (comp (ref "R1")
      (value "1K")
      (footprint "R-1206")
      (description "Resistor")
      (fields (field (name "PUBLISHER") "Altium Limited"))
      (libsource (lib "Discrete") (part "Resistor"))
    )
    (comp (ref "R2")
      (value "1K")
      (footprint "R-1206")
      (description "Resistor")
      (fields (field (name "PUBLISHER") "Altium Limited"))
      (libsource (lib "Discrete") (part "Resistor"))
    )
    (comp (ref "R3")
      (value "1K")
      (footprint "R-1206")
      (description "Resistor")
      (fields (field (name "PUBLISHER") "Altium Limited"))
      (libsource (lib "") (part "Resistor_1"))
    )
    (comp (ref "R4")
      (value "10K")
      (footprint "R-1206")
      (description "Resistor")
      (fields (field (name "PUBLISHER") "Altium Limited"))
      (libsource (lib "") (part "Resistor_2"))
    )
    (comp (ref "R5")
      (value "62K")
      (footprint "R-1206")
      (description "Resistor")
      (fields (field (name "PUBLISHER") "Altium Limited"))
      (libsource (lib "") (part "Resistor_2"))
    )
    (comp (ref "R6")
      (value "4K7")
      (footprint "R-1206")
      (description "Resistor")
      (fields (field (name "PUBLISHER") "Altium Limited"))
      (libsource (lib "") (part "Resistor_2"))
    )
    (comp (ref "R7")
      (value "10K")
      (footprint "R-1206")
      (description "Resistor")
      (fields (field (name "PUBLISHER") "Altium Limited"))
      (libsource (lib "") (part "Resistor_3"))
    )
    (comp (ref "R8")
      (value "1K")
      (footprint "R-1206")
      (description "Resistor")
      (fields (field (name "PUBLISHER") "Altium Limited"))
      (libsource (lib "") (part "Resistor_1"))
    )
    (comp (ref "R9")
      (value "10K")
      (footprint "R-1206")
      (description "Resistor")
      (fields (field (name "PUBLISHER") "Altium Limited"))
      (libsource (lib "") (part "Resistor_2"))
    )
    (comp (ref "R10")
      (value "47")
      (footprint "R-1206")
      (description "Resistor")
      (fields (field (name "PUBLISHER") "Altium Limited"))
      (libsource (lib "") (part "Resistor_1"))
    )
    (comp (ref "R11")
      (value "JZ")
      (footprint "R-1206")
      (description "Resistor")
      (fields (field (name "PUBLISHER") "Altium Limited"))
      (libsource (lib "") (part "Resistor_1"))
    )
    (comp (ref "R12")
      (value "47")
      (footprint "R-1206")
      (description "Resistor")
      (fields (field (name "PUBLISHER") "Altium Limited"))
      (libsource (lib "") (part "Resistor_1"))
    )
    (comp (ref "R13")
      (value "JZ")
      (footprint "R-1206")
      (description "Resistor")
      (fields (field (name "PUBLISHER") "Altium Limited"))
      (libsource (lib "") (part "Resistor_1"))
    )
    (comp (ref "R14")
      (value "4K7")
      (footprint "R-1206")
      (description "Resistor")
      (fields (field (name "PUBLISHER") "Altium Limited"))
      (libsource (lib "") (part "Resistor_2"))
    )
    (comp (ref "R15")
      (value "1K")
      (footprint "R-1206")
      (description "Resistor")
      (fields (field (name "PUBLISHER") "Altium Limited"))
      (libsource (lib "") (part "Resistor_1"))
    )
    (comp (ref "R16")
      (value "10K")
      (footprint "R-1206")
      (description "Resistor")
      (fields (field (name "PUBLISHER") "Altium Limited"))
      (libsource (lib "") (part "Resistor_3"))
    )
    (comp (ref "R17")
      (value "1K")
      (footprint "R-1206")
      (description "Resistor")
      (fields (field (name "PUBLISHER") "Altium Limited"))
      (libsource (lib "") (part "Resistor_1"))
    )
    (comp (ref "R18")
      (value "1K")
      (footprint "R-1206")
      (description "Resistor")
      (fields (field (name "PUBLISHER") "Altium Limited"))
      (libsource (lib "") (part "Resistor_1"))
    )
    (comp (ref "R19")
      (value "62K")
      (footprint "R-1206")
      (description "Resistor")
      (fields (field (name "PUBLISHER") "Altium Limited"))
      (libsource (lib "") (part "Resistor_2"))
    )
    (comp (ref "R20")
      (value "10K")
      (footprint "R-1206")
      (description "Resistor")
      (fields (field (name "PUBLISHER") "Altium Limited"))
      (libsource (lib "") (part "Resistor_2"))
    )
    (comp (ref "R21")
      (value "10K")
      (footprint "R-1206")
      (description "Resistor")
      (fields (field (name "PUBLISHER") "Altium Limited"))
      (libsource (lib "") (part "Resistor_2"))
    )
    (comp (ref "R22")
      (value "1K")
      (footprint "R-1206")
      (description "Resistor")
      (fields (field (name "PUBLISHER") "Altium Limited"))
      (libsource (lib "") (part "Resistor_1"))
    )
    (comp (ref "R23")
      (value "10K")
      (footprint "R-1206")
      (description "Resistor")
      (fields (field (name "PUBLISHER") "Altium Limited"))
      (libsource (lib "") (part "Resistor_2"))
    )
    (comp (ref "R24")
      (value "10K")
      (footprint "R-1206")
      (description "Resistor")
      (fields (field (name "PUBLISHER") "Altium Limited"))
      (libsource (lib "") (part "Resistor_2"))
    )
    (comp (ref "R25")
      (value "100")
      (footprint "R-1206")
      (description "Resistor")
      (fields (field (name "PUBLISHER") "Altium Limited"))
      (libsource (lib "Discrete") (part "Resistor"))
    )
    (comp (ref "R26")
      (value "100")
      (footprint "R-1206")
      (description "Resistor")
      (fields (field (name "PUBLISHER") "Altium Limited"))
      (libsource (lib "Discrete") (part "Resistor"))
    )
    (comp (ref "R27")
      (value "62K")
      (footprint "R-1206")
      (description "Resistor")
      (fields (field (name "PUBLISHER") "Altium Limited"))
      (libsource (lib "") (part "Resistor_2"))
    )
    (comp (ref "R28")
      (value "10K")
      (footprint "R-1206")
      (description "Resistor")
      (fields (field (name "PUBLISHER") "Altium Limited"))
      (libsource (lib "") (part "Resistor_2"))
    )
    (comp (ref "R29")
      (value "10K")
      (footprint "R-1206")
      (description "Resistor")
      (fields (field (name "PUBLISHER") "Altium Limited"))
      (libsource (lib "Discrete") (part "Resistor"))
    )
    (comp (ref "R30")
      (value "10K")
      (footprint "R-1206")
      (description "Resistor")
      (fields (field (name "PUBLISHER") "Altium Limited"))
      (libsource (lib "") (part "Resistor_2"))
    )
    (comp (ref "R31")
      (value "10K")
      (footprint "R-1206")
      (description "Resistor")
      (fields (field (name "PUBLISHER") "Altium Limited"))
      (libsource (lib "") (part "Resistor_2"))
    )
    (comp (ref "R32")
      (value "100")
      (footprint "R-1206")
      (description "Resistor")
      (fields (field (name "PUBLISHER") "Altium Limited"))
      (libsource (lib "Discrete") (part "Resistor"))
    )
    (comp (ref "R33")
      (value "10K")
      (footprint "R-1206")
      (description "Resistor")
      (fields (field (name "PUBLISHER") "Altium Limited"))
      (libsource (lib "") (part "Resistor_1"))
    )
    (comp (ref "R34")
      (value "100")
      (footprint "R-1206")
      (description "Resistor")
      (fields (field (name "PUBLISHER") "Altium Limited"))
      (libsource (lib "Discrete") (part "Resistor"))
    )
    (comp (ref "R35")
      (value "1M")
      (footprint "R-1206")
      (description "Resistor")
      (fields (field (name "PUBLISHER") "Altium Limited"))
      (libsource (lib "") (part "Resistor_1"))
    )
    (comp (ref "R36")
      (value "1K")
      (footprint "R-1206")
      (description "Resistor")
      (fields (field (name "PUBLISHER") "Altium Limited"))
      (libsource (lib "") (part "Resistor_1"))
    )
    (comp (ref "R37")
      (value "10K")
      (footprint "R-1206")
      (description "Resistor")
      (fields (field (name "PUBLISHER") "Altium Limited"))
      (libsource (lib "") (part "Resistor_1"))
    )
    (comp (ref "R38")
      (value "1M")
      (footprint "R-1206")
      (description "Resistor")
      (fields (field (name "PUBLISHER") "Altium Limited"))
      (libsource (lib "") (part "Resistor_1"))
    )
    (comp (ref "R39")
      (value "62K")
      (footprint "R-1206")
      (description "Resistor")
      (fields (field (name "PUBLISHER") "Altium Limited"))
      (libsource (lib "") (part "Resistor_2"))
    )
    (comp (ref "R40")
      (value "10K")
      (footprint "R-1206")
      (description "Resistor")
      (fields (field (name "PUBLISHER") "Altium Limited"))
      (libsource (lib "") (part "Resistor_2"))
    )
    (comp (ref "R41")
      (value "1K")
      (footprint "R-1206")
      (description "Resistor")
      (fields (field (name "PUBLISHER") "Altium Limited"))
      (libsource (lib "Discrete") (part "Resistor"))
    )
    (comp (ref "R42")
      (value "1K")
      (footprint "R-1206")
      (description "Resistor")
      (fields (field (name "PUBLISHER") "Altium Limited"))
      (libsource (lib "Discrete") (part "Resistor"))
    )
    (comp (ref "R43")
      (value "1M")
      (footprint "R-1206")
      (description "Resistor")
      (fields (field (name "PUBLISHER") "Altium Limited"))
      (libsource (lib "") (part "Resistor_1"))
    )
    (comp (ref "SW1")
      (value "PRG")
      (footprint "SW-DIP-01")
      (fields (field (name "Comment") "SW-DIP01"))
      (libsource (lib "Switches") (part "SW-DIP01"))
    )
    (comp (ref "SW2")
      (value "M3")
      (footprint "SW-SPST-4-B")
      (description "Switch Push Button OFF (ON) SPST Round Button 0.05A 24VDC Momentary Contact PC Pins Thru-Hole")
      (fields (field (name "MF") "TE Connectivity") (field (name "MP") "3-1825910-1"))
      (libsource (lib "Switches") (part "PushButton"))
    )
    (comp (ref "SW3")
      (value "M1")
      (footprint "SW-SPST-4-B")
      (description "Switch Push Button OFF (ON) SPST Round Button 0.05A 24VDC Momentary Contact PC Pins Thru-Hole")
      (fields (field (name "MF") "TE Connectivity") (field (name "MP") "3-1825910-1"))
      (libsource (lib "Switches") (part "PushButton"))
    )
    (comp (ref "SW4")
      (value "M2")
      (footprint "SW-SPST-4-B")
      (description "Switch Push Button OFF (ON) SPST Round Button 0.05A 24VDC Momentary Contact PC Pins Thru-Hole")
      (fields (field (name "MF") "TE Connectivity") (field (name "MP") "3-1825910-1"))
      (libsource (lib "Switches") (part "PushButton"))
    )
    (comp (ref "SW5")
      (value "M4")
      (footprint "SW-SPST-4-B")
      (description "Switch Push Button OFF (ON) SPST Round Button 0.05A 24VDC Momentary Contact PC Pins Thru-Hole")
      (fields (field (name "MF") "TE Connectivity") (field (name "MP") "3-1825910-1"))
      (libsource (lib "Switches") (part "PushButton"))
    )
    (comp (ref "SW6")
      (value "RESET")
      (footprint "SW-SPST-4")
      (description "Switch Push Button OFF (ON) SPST Round Button 0.05A 24VDC Momentary Contact PC Pins Thru-Hole")
      (fields (field (name "MF") "TE Connectivity") (field (name "MP") "3-1825910-1"))
      (libsource (lib "Switches") (part "PushButton"))
    )
    (comp (ref "SW7")
      (value "RESET")
      (footprint "SW-SPST-4")
      (description "Switch Push Button OFF (ON) SPST Round Button 0.05A 24VDC Momentary Contact PC Pins Thru-Hole")
      (fields (field (name "MF") "TE Connectivity") (field (name "MP") "3-1825910-1"))
      (libsource (lib "Switches") (part "PushButton"))
    )
    (comp (ref "T1")
      (value "CM Trans")
      (footprint "CM_UU9.8")
      (description "2 Line Common Mode Choke")
      (fields (field (name "MF") "Murata") (field (name "MP") "DLP11SN900HL2L"))
      (libsource (lib "Discrete") (part "CM Trans"))
    )
    (comp (ref "U1") (value "MAX487") (footprint "SOIC_8") (libsource (lib "Discrete") (part "MAX487")))
    (comp (ref "VR1")
      (value "LM2576-ADJ")
      (footprint "TO263_5")
      (description "SIMPLE SWITCHER&reg; 4V to 60V, 3A Low Component Count Step-Down Regulator 5-TO-220 -40 to 125")
      (fields (field (name "MP") "LM2576HVT-ADJ") (field (name "MF") "Texas Instruments"))
      (libsource (lib "Schlib1") (part "LM2576HVT-ADJ"))
    )
    (comp (ref "VR2")
      (value "LM2576-5V")
      (footprint "TO263_5")
      (description "SIMPLE SWITCHER&reg; 4V to 60V, 3A Low Component Count Step-Down Regulator 5-TO-220 -40 to 125")
      (fields (field (name "MP") "LM2576HVT-ADJ") (field (name "MF") "Texas Instruments"))
      (libsource (lib "Schlib1") (part "LM2576HVT-ADJ"))
    )
    (comp (ref "VR3")
      (value "LM2576-ADJ")
      (footprint "TO263_5")
      (description "SIMPLE SWITCHER&reg; 4V to 60V, 3A Low Component Count Step-Down Regulator 5-TO-220 -40 to 125")
      (fields (field (name "MP") "LM2576HVT-ADJ") (field (name "MF") "Texas Instruments"))
      (libsource (lib "Schlib1") (part "LM2576HVT-ADJ"))
    )
    (comp (ref "VR4")
      (value "LM2576-ADJ")
      (footprint "TO263_5")
      (description "SIMPLE SWITCHER&reg; 4V to 60V, 3A Low Component Count Step-Down Regulator 5-TO-220 -40 to 125")
      (fields (field (name "MP") "LM2576HVT-ADJ") (field (name "MF") "Texas Instruments"))
      (libsource (lib "Schlib1") (part "LM2576HVT-ADJ"))
    )
    (comp (ref "VR5")
      (value "LM2576-ADJ")
      (footprint "TO263_5")
      (description "SIMPLE SWITCHER&reg; 4V to 60V, 3A Low Component Count Step-Down Regulator 5-TO-220 -40 to 125")
      (fields (field (name "MP") "LM2576HVT-ADJ") (field (name "MF") "Texas Instruments"))
      (libsource (lib "Schlib1") (part "LM2576HVT-ADJ"))
    )
    (comp (ref "Y1")
      (value "Crystal")
      (footprint "Crystal")
      (fields (field (name "PARAMETER 1") "16MHz"))
      (libsource (lib "Discrete") (part "Crystal"))
    )
    (comp (ref "Y2")
      (value "Crystal")
      (footprint "Crystal")
      (fields (field (name "PARAMETER 1") "16MHz"))
      (libsource (lib "Discrete") (part "Crystal"))
    )
    (comp (ref "Y3")
      (value "Crystal")
      (footprint "Crystal")
      (fields (field (name "PARAMETER 1") "12MHz"))
      (libsource (lib "Discrete") (part "Crystal"))
    )
  )
  (nets
    (net (code "1") (name "/A") (class "Default")
      (node (ref "J1") (pin "3") (pintype "passive"))
      (node (ref "J5") (pin "3") (pintype "passive"))
      (node (ref "J6") (pin "3") (pintype "passive"))
      (node (ref "J8") (pin "3") (pintype "passive"))
      (node (ref "J9") (pin "3") (pintype "passive"))
      (node (ref "R13") (pin "2") (pinfunction "2_2") (pintype "passive"))
    )
    (net (code "2") (name "/B") (class "Default")
      (node (ref "J1") (pin "2") (pintype "passive"))
      (node (ref "J5") (pin "2") (pintype "passive"))
      (node (ref "J6") (pin "2") (pintype "passive"))
      (node (ref "J8") (pin "2") (pintype "passive"))
      (node (ref "J9") (pin "2") (pintype "passive"))
      (node (ref "R11") (pin "2") (pinfunction "2_2") (pintype "passive"))
    )
    (net (code "3") (name "/PA3") (class "Default")
      (node (ref "M2") (pin "48") (pinfunction "PA3_48") (pintype "passive"))
      (node (ref "R18") (pin "1") (pinfunction "1_1") (pintype "passive"))
    )
    (net (code "4") (name "/PB1") (class "Default")
      (node (ref "H2") (pin "5") (pintype "passive"))
      (node (ref "M2") (pin "11") (pinfunction "PB1/SCK_11") (pintype "passive"))
    )
    (net (code "5") (name "/PB1'") (class "Default")
      (node (ref "H1") (pin "5") (pintype "passive"))
      (node (ref "M1") (pin "11") (pinfunction "PB1/SCK_11") (pintype "passive"))
    )
    (net (code "6") (name "/PB4") (class "Default")
      (node (ref "J3") (pin "2") (pintype "passive"))
      (node (ref "M2") (pin "14") (pinfunction "PB4_14") (pintype "passive"))
    )
    (net (code "7") (name "/PB5") (class "Default")
      (node (ref "J7") (pin "2") (pintype "passive"))
      (node (ref "M2") (pin "15") (pinfunction "PB5_15") (pintype "passive"))
    )
    (net (code "8") (name "/PB6") (class "Default")
      (node (ref "J10") (pin "2") (pintype "passive"))
      (node (ref "M2") (pin "16") (pinfunction "PB6_16") (pintype "passive"))
    )
    (net (code "9") (name "/PB7") (class "Default")
      (node (ref "J11") (pin "2") (pintype "passive"))
      (node (ref "M2") (pin "17") (pinfunction "PB7_17") (pintype "passive"))
    )
    (net (code "10") (name "/PD2") (class "Default")
      (node (ref "H4") (pin "5") (pintype "input"))
      (node (ref "M2") (pin "27") (pinfunction "PD2/RXD1_27") (pintype "passive"))
    )
    (net (code "11") (name "/PD2'") (class "Default")
      (node (ref "D4") (pin "2") (pinfunction "K_2") (pintype "passive"))
      (node (ref "M1") (pin "27") (pinfunction "PD2/RXD1_27") (pintype "passive"))
      (node (ref "R4") (pin "1") (pinfunction "1_1") (pintype "passive"))
      (node (ref "U1") (pin "1") (pinfunction "R_1") (pintype "passive"))
    )
    (net (code "12") (name "/PD3") (class "Default")
      (node (ref "H4") (pin "4") (pintype "input"))
      (node (ref "M2") (pin "28") (pinfunction "PD3/TXD1_28") (pintype "passive"))
    )
    (net (code "13") (name "/PD3'") (class "Default")
      (node (ref "D3") (pin "2") (pinfunction "K_2") (pintype "passive"))
      (node (ref "M1") (pin "28") (pinfunction "PD3/TXD1_28") (pintype "passive"))
      (node (ref "U1") (pin "4") (pinfunction "D_4") (pintype "passive"))
    )
    (net (code "14") (name "/PD4'") (class "Default")
      (node (ref "M1") (pin "29") (pinfunction "PD4_29") (pintype "passive"))
      (node (ref "U1") (pin "2") (pinfunction "RE_2") (pintype "passive"))
      (node (ref "U1") (pin "3") (pinfunction "DE_3") (pintype "passive"))
    )
    (net (code "15") (name "/PE0") (class "Default")
      (node (ref "H2") (pin "3") (pintype "passive"))
      (node (ref "M2") (pin "2") (pinfunction "PE0/RXD0_2") (pintype "passive"))
    )
    (net (code "16") (name "/PE0'") (class "Default")
      (node (ref "D19") (pin "1") (pinfunction "A_1") (pintype "passive"))
      (node (ref "D26") (pin "2") (pinfunction "K_2") (pintype "passive"))
      (node (ref "D28") (pin "1") (pinfunction "A_1") (pintype "passive"))
      (node (ref "R29") (pin "2") (pinfunction "2_2") (pintype "passive"))
      (node (ref "SW1") (pin "1") (pinfunction "1_1") (pintype "passive"))
    )
    (net (code "17") (name "/PE1") (class "Default")
      (node (ref "H2") (pin "4") (pintype "passive"))
      (node (ref "M2") (pin "3") (pinfunction "PE1/TXD0_3") (pintype "passive"))
    )
    (net (code "18") (name "/PE1'") (class "Default")
      (node (ref "D25") (pin "2") (pinfunction "K_2") (pintype "passive"))
      (node (ref "H1") (pin "4") (pintype "passive"))
      (node (ref "H3") (pin "4") (pintype "input"))
      (node (ref "M1") (pin "3") (pinfunction "PE1/TXD0_3") (pintype "passive"))
      (node (ref "M3") (pin "3") (pinfunction "RXD_3") (pintype "passive"))
    )
    (net (code "19") (name "/PE2") (class "Default")
      (node (ref "C35") (pin "2") (pinfunction "2_2") (pintype "passive"))
      (node (ref "M2") (pin "4") (pinfunction "PE2_4") (pintype "passive"))
      (node (ref "R24") (pin "1") (pinfunction "1_1") (pintype "passive"))
      (node (ref "R26") (pin "2") (pinfunction "2_2") (pintype "passive"))
    )
    (net (code "20") (name "/PE3") (class "Default")
      (node (ref "C43") (pin "2") (pinfunction "2_2") (pintype "passive"))
      (node (ref "M2") (pin "5") (pinfunction "PE3_5") (pintype "passive"))
      (node (ref "R30") (pin "1") (pinfunction "1_1") (pintype "passive"))
      (node (ref "R32") (pin "2") (pinfunction "2_2") (pintype "passive"))
    )
    (net (code "21") (name "/PE4") (class "Default")
      (node (ref "C34") (pin "2") (pinfunction "2_2") (pintype "passive"))
      (node (ref "M2") (pin "6") (pinfunction "PE4_6") (pintype "passive"))
      (node (ref "R23") (pin "1") (pinfunction "1_1") (pintype "passive"))
      (node (ref "R25") (pin "2") (pinfunction "2_2") (pintype "passive"))
    )
    (net (code "22") (name "/PE5") (class "Default")
      (node (ref "C44") (pin "2") (pinfunction "2_2") (pintype "passive"))
      (node (ref "M2") (pin "7") (pinfunction "PE5_7") (pintype "passive"))
      (node (ref "R31") (pin "1") (pinfunction "1_1") (pintype "passive"))
      (node (ref "R34") (pin "2") (pinfunction "2_2") (pintype "passive"))
    )
    (net (code "23") (name "/RESET") (class "Default")
      (node (ref "C50") (pin "2") (pinfunction "2_2") (pintype "passive"))
      (node (ref "D23") (pin "2") (pinfunction "K_2") (pintype "passive"))
      (node (ref "H2") (pin "6") (pintype "passive"))
      (node (ref "M2") (pin "20") (pinfunction "RESET_20") (pintype "passive"))
      (node (ref "R37") (pin "2") (pinfunction "2_2") (pintype "passive"))
      (node (ref "SW7") (pin "2") (pinfunction "2_2") (pintype "passive"))
    )
    (net (code "24") (name "/RESET'") (class "Default")
      (node (ref "C45") (pin "2") (pinfunction "2_2") (pintype "passive"))
      (node (ref "D20") (pin "2") (pinfunction "K_2") (pintype "passive"))
      (node (ref "H1") (pin "6") (pintype "passive"))
      (node (ref "M1") (pin "20") (pinfunction "RESET_20") (pintype "passive"))
      (node (ref "R33") (pin "2") (pinfunction "2_2") (pintype "passive"))
      (node (ref "SW6") (pin "2") (pinfunction "2_2") (pintype "passive"))
    )
    (net (code "25") (name "/USB_D_N") (class "Default")
      (node (ref "J12") (pin "2") (pinfunction "2_2") (pintype "passive"))
      (node (ref "M3") (pin "6") (pinfunction "D-_6") (pintype "passive"))
    )
    (net (code "26") (name "/USB_D_P") (class "Default")
      (node (ref "J12") (pin "3") (pinfunction "3_3") (pintype "passive"))
      (node (ref "M3") (pin "5") (pinfunction "D+_5") (pintype "passive"))
    )
    (net (code "27") (name "GND") (class "Default")
      (node (ref "C1") (pin "2") (pinfunction "2_2") (pintype "passive"))
      (node (ref "C10") (pin "1") (pinfunction "1_1") (pintype "passive"))
      (node (ref "C11") (pin "1") (pinfunction "1_1") (pintype "passive"))
      (node (ref "C12") (pin "1") (pinfunction "1_1") (pintype "passive"))
      (node (ref "C14") (pin "1") (pinfunction "1_1") (pintype "passive"))
      (node (ref "C15") (pin "2") (pinfunction "2_2") (pintype "passive"))
      (node (ref "C16") (pin "1") (pinfunction "1_1") (pintype "passive"))
      (node (ref "C17") (pin "2") (pinfunction "2_2") (pintype "passive"))
      (node (ref "C18") (pin "1") (pinfunction "1_1") (pintype "passive"))
      (node (ref "C19") (pin "1") (pinfunction "1_1") (pintype "passive"))
      (node (ref "C2") (pin "1") (pinfunction "1_1") (pintype "passive"))
      (node (ref "C20") (pin "2") (pinfunction "2_2") (pintype "passive"))
      (node (ref "C21") (pin "1") (pinfunction "1_1") (pintype "passive"))
      (node (ref "C22") (pin "2") (pinfunction "2_2") (pintype "passive"))
      (node (ref "C23") (pin "1") (pinfunction "1_1") (pintype "passive"))
      (node (ref "C24") (pin "2") (pinfunction "2_2") (pintype "passive"))
      (node (ref "C25") (pin "2") (pinfunction "2_2") (pintype "passive"))
      (node (ref "C26") (pin "1") (pinfunction "1_1") (pintype "passive"))
      (node (ref "C27") (pin "1") (pinfunction "1_1") (pintype "passive"))
      (node (ref "C28") (pin "1") (pinfunction "1_1") (pintype "passive"))
      (node (ref "C29") (pin "2") (pinfunction "2_2") (pintype "passive"))
      (node (ref "C3") (pin "1") (pinfunction "1_1") (pintype "passive"))
      (node (ref "C30") (pin "1") (pinfunction "1_1") (pintype "passive"))
      (node (ref "C31") (pin "2") (pinfunction "2_2") (pintype "passive"))
      (node (ref "C32") (pin "1") (pinfunction "1_1") (pintype "passive"))
      (node (ref "C33") (pin "2") (pinfunction "2_2") (pintype "passive"))
      (node (ref "C34") (pin "1") (pinfunction "1_1") (pintype "passive"))
      (node (ref "C35") (pin "1") (pinfunction "1_1") (pintype "passive"))
      (node (ref "C36") (pin "1") (pinfunction "1_1") (pintype "passive"))
      (node (ref "C37") (pin "2") (pinfunction "2_2") (pintype "passive"))
      (node (ref "C38") (pin "2") (pinfunction "2_2") (pintype "passive"))
      (node (ref "C39") (pin "1") (pinfunction "1_1") (pintype "passive"))
      (node (ref "C4") (pin "1") (pinfunction "1_1") (pintype "passive"))
      (node (ref "C40") (pin "1") (pinfunction "1_1") (pintype "passive"))
      (node (ref "C41") (pin "1") (pinfunction "1_1") (pintype "passive"))
      (node (ref "C42") (pin "1") (pinfunction "1_1") (pintype "passive"))
      (node (ref "C43") (pin "1") (pinfunction "1_1") (pintype "passive"))
      (node (ref "C44") (pin "1") (pinfunction "1_1") (pintype "passive"))
      (node (ref "C45") (pin "1") (pinfunction "1_1") (pintype "passive"))
      (node (ref "C46") (pin "1") (pinfunction "1_1") (pintype "passive"))
      (node (ref "C47") (pin "1") (pinfunction "1_1") (pintype "passive"))
      (node (ref "C48") (pin "1") (pinfunction "1_1") (pintype "passive"))
      (node (ref "C49") (pin "1") (pinfunction "1_1") (pintype "passive"))
      (node (ref "C5") (pin "2") (pinfunction "2_2") (pintype "passive"))
      (node (ref "C50") (pin "1") (pinfunction "1_1") (pintype "passive"))
      (node (ref "C51") (pin "2") (pinfunction "2_2") (pintype "passive"))
      (node (ref "C52") (pin "1") (pinfunction "1_1") (pintype "passive"))
      (node (ref "C53") (pin "1") (pinfunction "1_1") (pintype "passive"))
      (node (ref "C54") (pin "1") (pinfunction "1_1") (pintype "passive"))
      (node (ref "C55") (pin "2") (pinfunction "2_2") (pintype "passive"))
      (node (ref "C56") (pin "2") (pinfunction "2_2") (pintype "passive"))
      (node (ref "C57") (pin "1") (pinfunction "1_1") (pintype "passive"))
      (node (ref "C58") (pin "1") (pinfunction "1_1") (pintype "passive"))
      (node (ref "C59") (pin "1") (pinfunction "1_1") (pintype "passive"))
      (node (ref "C6") (pin "1") (pinfunction "1_1") (pintype "passive"))
      (node (ref "C60") (pin "1") (pinfunction "1_1") (pintype "passive"))
      (node (ref "C61") (pin "1") (pinfunction "1_1") (pintype "passive"))
      (node (ref "C62") (pin "1") (pinfunction "1_1") (pintype "passive"))
      (node (ref "C63") (pin "1") (pinfunction "1_1") (pintype "passive"))
      (node (ref "C64") (pin "1") (pinfunction "1_1") (pintype "passive"))
      (node (ref "C65") (pin "1") (pinfunction "1_1") (pintype "passive"))
      (node (ref "C66") (pin "1") (pinfunction "1_1") (pintype "passive"))
      (node (ref "C67") (pin "1") (pinfunction "1_1") (pintype "passive"))
      (node (ref "C7") (pin "2") (pinfunction "2_2") (pintype "passive"))
      (node (ref "C8") (pin "2") (pinfunction "2_2") (pintype "passive"))
      (node (ref "C9") (pin "2") (pinfunction "2_2") (pintype "passive"))
      (node (ref "D1") (pin "2") (pinfunction "K_2") (pintype "passive"))
      (node (ref "D10") (pin "1") (pinfunction "A_1") (pintype "passive"))
      (node (ref "D12") (pin "1") (pinfunction "A_1") (pintype "passive"))
      (node (ref "D13") (pin "2") (pinfunction "K_2") (pintype "passive"))
      (node (ref "D15") (pin "1") (pinfunction "A_1") (pintype "passive"))
      (node (ref "D16") (pin "2") (pinfunction "K_2") (pintype "passive"))
      (node (ref "D18") (pin "1") (pinfunction "A_1") (pintype "passive"))
      (node (ref "D20") (pin "1") (pinfunction "A_1") (pintype "passive"))
      (node (ref "D21") (pin "2") (pinfunction "K_2") (pintype "passive"))
      (node (ref "D23") (pin "1") (pinfunction "A_1") (pintype "passive"))
      (node (ref "D24") (pin "1") (pinfunction "A_1") (pintype "passive"))
      (node (ref "D6") (pin "2") (pinfunction "K_2") (pintype "passive"))
      (node (ref "D8") (pin "1") (pinfunction "A_1") (pintype "passive"))
      (node (ref "D9") (pin "1") (pinfunction "A_1") (pintype "passive"))
      (node (ref "H1") (pin "2") (pintype "passive"))
      (node (ref "H2") (pin "2") (pintype "passive"))
      (node (ref "H3") (pin "1") (pintype "input"))
      (node (ref "H3") (pin "3") (pintype "input"))
      (node (ref "H4") (pin "1") (pintype "input"))
      (node (ref "H4") (pin "3") (pintype "input"))
      (node (ref "J1") (pin "1") (pintype "passive"))
      (node (ref "J10") (pin "1") (pintype "passive"))
      (node (ref "J11") (pin "1") (pintype "passive"))
      (node (ref "J12") (pin "4") (pinfunction "4_4") (pintype "passive"))
      (node (ref "J3") (pin "1") (pintype "passive"))
      (node (ref "J5") (pin "1") (pintype "passive"))
      (node (ref "J6") (pin "1") (pintype "passive"))
      (node (ref "J7") (pin "1") (pintype "passive"))
      (node (ref "J8") (pin "1") (pintype "passive"))
      (node (ref "J9") (pin "1") (pintype "passive"))
      (node (ref "M1") (pin "22") (pinfunction "GND_22") (pintype "passive"))
      (node (ref "M1") (pin "53") (pinfunction "GND_53") (pintype "passive"))
      (node (ref "M1") (pin "63") (pinfunction "GND_63") (pintype "passive"))
      (node (ref "M2") (pin "22") (pinfunction "GND_22") (pintype "passive"))
      (node (ref "M2") (pin "53") (pinfunction "GND_53") (pintype "passive"))
      (node (ref "M2") (pin "63") (pinfunction "GND_63") (pintype "passive"))
      (node (ref "M3") (pin "1") (pinfunction "GND_1") (pintype "passive"))
      (node (ref "Q1") (pin "3") (pinfunction "E_3") (pintype "passive"))
      (node (ref "Q2") (pin "3") (pinfunction "E_3") (pintype "passive"))
      (node (ref "R16") (pin "2") (pinfunction "2_2") (pintype "passive"))
      (node (ref "R20") (pin "1") (pinfunction "1_1") (pintype "passive"))
      (node (ref "R21") (pin "1") (pinfunction "1_1") (pintype "passive"))
      (node (ref "R28") (pin "1") (pinfunction "1_1") (pintype "passive"))
      (node (ref "R40") (pin "1") (pinfunction "1_1") (pintype "passive"))
      (node (ref "R6") (pin "2") (pinfunction "2_2") (pintype "passive"))
      (node (ref "R9") (pin "1") (pinfunction "1_1") (pintype "passive"))
      (node (ref "SW2") (pin "1") (pinfunction "1_1") (pintype "passive"))
      (node (ref "SW3") (pin "1") (pinfunction "1_1") (pintype "passive"))
      (node (ref "SW4") (pin "1") (pinfunction "1_1") (pintype "passive"))
      (node (ref "SW5") (pin "1") (pinfunction "1_1") (pintype "passive"))
      (node (ref "SW6") (pin "1") (pinfunction "1_1") (pintype "passive"))
      (node (ref "SW7") (pin "1") (pinfunction "1_1") (pintype "passive"))
      (node (ref "T1") (pin "4") (pinfunction "3_4") (pintype "passive"))
      (node (ref "U1") (pin "5") (pinfunction "GND_5") (pintype "passive"))
      (node (ref "VR1") (pin "3") (pinfunction "GROUND_3") (pintype "passive"))
      (node (ref "VR1") (pin "5") (pinfunction "~{ON}/OFF_5") (pintype "passive"))
      (node (ref "VR2") (pin "3") (pinfunction "GROUND_3") (pintype "passive"))
      (node (ref "VR3") (pin "3") (pinfunction "GROUND_3") (pintype "passive"))
      (node (ref "VR3") (pin "5") (pinfunction "~{ON}/OFF_5") (pintype "passive"))
      (node (ref "VR4") (pin "3") (pinfunction "GROUND_3") (pintype "passive"))
      (node (ref "VR4") (pin "5") (pinfunction "~{ON}/OFF_5") (pintype "passive"))
      (node (ref "VR5") (pin "3") (pinfunction "GROUND_3") (pintype "passive"))
      (node (ref "VR5") (pin "5") (pinfunction "~{ON}/OFF_5") (pintype "passive"))
    )
    (net (code "28") (name "Net-(C11-Pad2)") (class "Default")
      (node (ref "C11") (pin "2") (pinfunction "2_2") (pintype "passive"))
      (node (ref "C12") (pin "2") (pinfunction "2_2") (pintype "passive"))
      (node (ref "C8") (pin "1") (pinfunction "1_1") (pintype "passive"))
      (node (ref "C9") (pin "1") (pinfunction "1_1") (pintype "passive"))
      (node (ref "J3") (pin "3") (pintype "passive"))
      (node (ref "L1") (pin "2") (pinfunction "2_2") (pintype "passive"))
      (node (ref "R3") (pin "1") (pinfunction "1_1") (pintype "passive"))
      (node (ref "R5") (pin "2") (pinfunction "2_2") (pintype "passive"))
    )
    (net (code "29") (name "Net-(C24-Pad1)") (class "Default")
      (node (ref "C24") (pin "1") (pinfunction "1_1") (pintype "passive"))
      (node (ref "C25") (pin "1") (pinfunction "1_1") (pintype "passive"))
      (node (ref "C27") (pin "2") (pinfunction "2_2") (pintype "passive"))
      (node (ref "C28") (pin "2") (pinfunction "2_2") (pintype "passive"))
      (node (ref "J7") (pin "3") (pintype "passive"))
      (node (ref "L3") (pin "2") (pinfunction "2_2") (pintype "passive"))
      (node (ref "R17") (pin "1") (pinfunction "1_1") (pintype "passive"))
      (node (ref "R19") (pin "2") (pinfunction "2_2") (pintype "passive"))
    )
    (net (code "30") (name "Net-(C37-Pad1)") (class "Default")
      (node (ref "C37") (pin "1") (pinfunction "1_1") (pintype "passive"))
      (node (ref "C38") (pin "1") (pinfunction "1_1") (pintype "passive"))
      (node (ref "C39") (pin "2") (pinfunction "2_2") (pintype "passive"))
      (node (ref "C40") (pin "2") (pinfunction "2_2") (pintype "passive"))
      (node (ref "J10") (pin "3") (pintype "passive"))
      (node (ref "L4") (pin "2") (pinfunction "2_2") (pintype "passive"))
      (node (ref "R22") (pin "1") (pinfunction "1_1") (pintype "passive"))
      (node (ref "R27") (pin "2") (pinfunction "2_2") (pintype "passive"))
    )
    (net (code "31") (name "Net-(C55-Pad1)") (class "Default")
      (node (ref "C55") (pin "1") (pinfunction "1_1") (pintype "passive"))
      (node (ref "C56") (pin "1") (pinfunction "1_1") (pintype "passive"))
      (node (ref "C57") (pin "2") (pinfunction "2_2") (pintype "passive"))
      (node (ref "C58") (pin "2") (pinfunction "2_2") (pintype "passive"))
      (node (ref "J11") (pin "3") (pintype "passive"))
      (node (ref "L5") (pin "2") (pinfunction "2_2") (pintype "passive"))
      (node (ref "R36") (pin "1") (pinfunction "1_1") (pintype "passive"))
      (node (ref "R39") (pin "2") (pinfunction "2_2") (pintype "passive"))
    )
    (net (code "32") (name "Net-(C67-Pad2)") (class "Default")
      (node (ref "C67") (pin "2") (pinfunction "2_2") (pintype "passive"))
      (node (ref "J12") (pin "S1") (pinfunction "SHIELD_S1") (pintype "passive"))
      (node (ref "J12") (pin "S2") (pinfunction "SHIELD_S2") (pintype "passive"))
    )
    (net (code "33") (name "Net-(D1-A)") (class "Default")
      (node (ref "D1") (pin "1") (pinfunction "A_1") (pintype "passive"))
      (node (ref "R3") (pin "2") (pinfunction "2_2") (pintype "passive"))
    )
    (net (code "34") (name "Net-(D2-K)") (class "Default")
      (node (ref "C5") (pin "1") (pinfunction "1_1") (pintype "passive"))
      (node (ref "C6") (pin "2") (pinfunction "2_2") (pintype "passive"))
      (node (ref "D2") (pin "2") (pinfunction "K_2") (pintype "passive"))
      (node (ref "VR1") (pin "1") (pinfunction "VIN_1") (pintype "passive"))
    )
    (net (code "35") (name "Net-(D3-A)") (class "Default")
      (node (ref "D3") (pin "1") (pinfunction "A_1") (pintype "passive"))
      (node (ref "R1") (pin "2") (pinfunction "2_2") (pintype "passive"))
    )
    (net (code "36") (name "Net-(D4-A)") (class "Default")
      (node (ref "D4") (pin "1") (pinfunction "A_1") (pintype "passive"))
      (node (ref "R2") (pin "2") (pinfunction "2_2") (pintype "passive"))
    )
    (net (code "37") (name "Net-(D5-K)") (class "Default")
      (node (ref "D5") (pin "2") (pinfunction "K_2") (pintype "passive"))
      (node (ref "F1") (pin "1") (pinfunction "1_1") (pintype "passive"))
    )
    (net (code "38") (name "Net-(D6-A)") (class "Default")
      (node (ref "D6") (pin "1") (pinfunction "A_1") (pintype "passive"))
      (node (ref "R8") (pin "2") (pinfunction "2_2") (pintype "passive"))
    )
    (net (code "39") (name "Net-(D7-A)") (class "Default")
      (node (ref "C13") (pin "1") (pinfunction "1_1") (pintype "passive"))
      (node (ref "D7") (pin "1") (pinfunction "A_1") (pintype "passive"))
      (node (ref "J4") (pin "2") (pintype "passive"))
      (node (ref "T1") (pin "3") (pinfunction "4_3") (pintype "passive"))
    )
    (net (code "40") (name "Net-(D7-K)") (class "Default")
      (node (ref "C13") (pin "2") (pinfunction "2_2") (pintype "passive"))
      (node (ref "D7") (pin "2") (pinfunction "K_2") (pintype "passive"))
      (node (ref "F1") (pin "2") (pinfunction "2_2") (pintype "passive"))
      (node (ref "T1") (pin "1") (pinfunction "1_1") (pintype "passive"))
    )
    (net (code "41") (name "Net-(D8-K)") (class "Default")
      (node (ref "D8") (pin "2") (pinfunction "K_2") (pintype "passive"))
      (node (ref "L1") (pin "1") (pinfunction "1_1") (pintype "passive"))
      (node (ref "VR1") (pin "2") (pinfunction "OUTPUT_2") (pintype "passive"))
    )
    (net (code "42") (name "Net-(D9-K)") (class "Default")
      (node (ref "D9") (pin "2") (pinfunction "K_2") (pintype "passive"))
      (node (ref "L2") (pin "1") (pinfunction "1_1") (pintype "passive"))
      (node (ref "VR2") (pin "2") (pinfunction "OUTPUT_2") (pintype "passive"))
    )
    (net (code "43") (name "Net-(D11-A)") (class "Default")
      (node (ref "D11") (pin "1") (pinfunction "A_1") (pintype "passive"))
      (node (ref "R15") (pin "1") (pinfunction "1_1") (pintype "passive"))
    )
    (net (code "44") (name "Net-(D12-K-Pad2)") (class "Default")
      (node (ref "D12") (pin "2") (pinfunction "K_2") (pintype "passive"))
      (node (ref "R10") (pin "2") (pinfunction "2_2") (pintype "passive"))
      (node (ref "R11") (pin "1") (pinfunction "1_1") (pintype "passive"))
      (node (ref "R6") (pin "1") (pinfunction "1_1") (pintype "passive"))
    )
    (net (code "45") (name "Net-(D12-K-Pad3)") (class "Default")
      (node (ref "D12") (pin "3") (pinfunction "K_3") (pintype "passive"))
      (node (ref "R12") (pin "2") (pinfunction "2_2") (pintype "passive"))
      (node (ref "R13") (pin "1") (pinfunction "1_1") (pintype "passive"))
      (node (ref "R14") (pin "2") (pinfunction "2_2") (pintype "passive"))
    )
    (net (code "46") (name "Net-(D13-A)") (class "Default")
      (node (ref "D13") (pin "1") (pinfunction "A_1") (pintype "passive"))
      (node (ref "R17") (pin "2") (pinfunction "2_2") (pintype "passive"))
    )
    (net (code "47") (name "Net-(D14-K)") (class "Default")
      (node (ref "C22") (pin "1") (pinfunction "1_1") (pintype "passive"))
      (node (ref "C23") (pin "2") (pinfunction "2_2") (pintype "passive"))
      (node (ref "D14") (pin "2") (pinfunction "K_2") (pintype "passive"))
      (node (ref "VR3") (pin "1") (pinfunction "VIN_1") (pintype "passive"))
    )
    (net (code "48") (name "Net-(D15-K)") (class "Default")
      (node (ref "D15") (pin "2") (pinfunction "K_2") (pintype "passive"))
      (node (ref "L3") (pin "1") (pinfunction "1_1") (pintype "passive"))
      (node (ref "VR3") (pin "2") (pinfunction "OUTPUT_2") (pintype "passive"))
    )
    (net (code "49") (name "Net-(D16-A)") (class "Default")
      (node (ref "D16") (pin "1") (pinfunction "A_1") (pintype "passive"))
      (node (ref "R22") (pin "2") (pinfunction "2_2") (pintype "passive"))
    )
    (net (code "50") (name "Net-(D17-K)") (class "Default")
      (node (ref "C33") (pin "1") (pinfunction "1_1") (pintype "passive"))
      (node (ref "C36") (pin "2") (pinfunction "2_2") (pintype "passive"))
      (node (ref "D17") (pin "2") (pinfunction "K_2") (pintype "passive"))
      (node (ref "VR4") (pin "1") (pinfunction "VIN_1") (pintype "passive"))
    )
    (net (code "51") (name "Net-(D18-K)") (class "Default")
      (node (ref "D18") (pin "2") (pinfunction "K_2") (pintype "passive"))
      (node (ref "L4") (pin "1") (pinfunction "1_1") (pintype "passive"))
      (node (ref "VR4") (pin "2") (pinfunction "OUTPUT_2") (pintype "passive"))
    )
    (net (code "52") (name "Net-(D19-K)") (class "Default")
      (node (ref "D19") (pin "2") (pinfunction "K_2") (pintype "passive"))
      (node (ref "H3") (pin "5") (pintype "input"))
    )
    (net (code "53") (name "Net-(D21-A)") (class "Default")
      (node (ref "D21") (pin "1") (pinfunction "A_1") (pintype "passive"))
      (node (ref "R36") (pin "2") (pinfunction "2_2") (pintype "passive"))
    )
    (net (code "54") (name "Net-(D22-K)") (class "Default")
      (node (ref "C51") (pin "1") (pinfunction "1_1") (pintype "passive"))
      (node (ref "C54") (pin "2") (pinfunction "2_2") (pintype "passive"))
      (node (ref "D22") (pin "2") (pinfunction "K_2") (pintype "passive"))
      (node (ref "VR5") (pin "1") (pinfunction "VIN_1") (pintype "passive"))
    )
    (net (code "55") (name "Net-(D24-K)") (class "Default")
      (node (ref "D24") (pin "2") (pinfunction "K_2") (pintype "passive"))
      (node (ref "L5") (pin "1") (pinfunction "1_1") (pintype "passive"))
      (node (ref "VR5") (pin "2") (pinfunction "OUTPUT_2") (pintype "passive"))
    )
    (net (code "56") (name "Net-(D25-A)") (class "Default")
      (node (ref "D25") (pin "1") (pinfunction "A_1") (pintype "passive"))
      (node (ref "R41") (pin "2") (pinfunction "2_2") (pintype "passive"))
    )
    (net (code "57") (name "Net-(D26-A)") (class "Default")
      (node (ref "D26") (pin "1") (pinfunction "A_1") (pintype "passive"))
      (node (ref "R42") (pin "2") (pinfunction "2_2") (pintype "passive"))
    )
    (net (code "58") (name "Net-(D28-K)") (class "Default")
      (node (ref "D28") (pin "2") (pinfunction "K_2") (pintype "passive"))
      (node (ref "M3") (pin "2") (pinfunction "TXD_2") (pintype "passive"))
    )
    (net (code "59") (name "Net-(J2-Pad2)") (class "Default")
      (node (ref "J2") (pin "2") (pintype "passive"))
      (node (ref "J4") (pin "1") (pintype "passive"))
    )
    (net (code "60") (name "Net-(M1-PE0{slash}RXD0)") (class "Default")
      (node (ref "H1") (pin "3") (pintype "passive"))
      (node (ref "M1") (pin "2") (pinfunction "PE0/RXD0_2") (pintype "passive"))
      (node (ref "SW1") (pin "2") (pinfunction "2_2") (pintype "passive"))
    )
    (net (code "61") (name "Net-(M1-XTAL1)") (class "Default")
      (node (ref "C49") (pin "2") (pinfunction "2_2") (pintype "passive"))
      (node (ref "M1") (pin "24") (pinfunction "XTAL1_24") (pintype "passive"))
      (node (ref "R35") (pin "2") (pinfunction "2_2") (pintype "passive"))
      (node (ref "Y1") (pin "2") (pinfunction "2_2") (pintype "passive"))
    )
    (net (code "62") (name "Net-(M1-XTAL2)") (class "Default")
      (node (ref "C48") (pin "2") (pinfunction "2_2") (pintype "passive"))
      (node (ref "M1") (pin "23") (pinfunction "XTAL2_23") (pintype "passive"))
      (node (ref "R35") (pin "1") (pinfunction "1_1") (pintype "passive"))
      (node (ref "Y1") (pin "1") (pinfunction "1_1") (pintype "passive"))
    )
    (net (code "63") (name "Net-(M2-XTAL1)") (class "Default")
      (node (ref "C60") (pin "2") (pinfunction "2_2") (pintype "passive"))
      (node (ref "M2") (pin "24") (pinfunction "XTAL1_24") (pintype "passive"))
      (node (ref "R38") (pin "2") (pinfunction "2_2") (pintype "passive"))
      (node (ref "Y2") (pin "2") (pinfunction "2_2") (pintype "passive"))
    )
    (net (code "64") (name "Net-(M2-XTAL2)") (class "Default")
      (node (ref "C59") (pin "2") (pinfunction "2_2") (pintype "passive"))
      (node (ref "M2") (pin "23") (pinfunction "XTAL2_23") (pintype "passive"))
      (node (ref "R38") (pin "1") (pinfunction "1_1") (pintype "passive"))
      (node (ref "Y2") (pin "1") (pinfunction "1_1") (pintype "passive"))
    )
    (net (code "65") (name "Net-(M3-V3)") (class "Default")
      (node (ref "C64") (pin "2") (pinfunction "2_2") (pintype "passive"))
      (node (ref "M3") (pin "4") (pinfunction "V3_4") (pintype "passive"))
    )
    (net (code "66") (name "Net-(M3-XI)") (class "Default")
      (node (ref "C65") (pin "2") (pinfunction "2_2") (pintype "passive"))
      (node (ref "M3") (pin "7") (pinfunction "XI_7") (pintype "passive"))
      (node (ref "R43") (pin "1") (pinfunction "1_1") (pintype "passive"))
      (node (ref "Y3") (pin "1") (pinfunction "1_1") (pintype "passive"))
    )
    (net (code "67") (name "Net-(M3-XO)") (class "Default")
      (node (ref "C66") (pin "2") (pinfunction "2_2") (pintype "passive"))
      (node (ref "M3") (pin "8") (pinfunction "XO_8") (pintype "passive"))
      (node (ref "R43") (pin "2") (pinfunction "2_2") (pintype "passive"))
      (node (ref "Y3") (pin "2") (pinfunction "2_2") (pintype "passive"))
    )
    (net (code "68") (name "Net-(Q1-B)") (class "Default")
      (node (ref "C19") (pin "2") (pinfunction "2_2") (pintype "passive"))
      (node (ref "Q1") (pin "2") (pinfunction "B_2") (pintype "passive"))
      (node (ref "R15") (pin "2") (pinfunction "2_2") (pintype "passive"))
      (node (ref "R16") (pin "1") (pinfunction "1_1") (pintype "passive"))
    )
    (net (code "69") (name "Net-(Q1-C)") (class "Default")
      (node (ref "Q1") (pin "1") (pinfunction "C_1") (pintype "passive"))
      (node (ref "R7") (pin "2") (pinfunction "2_2") (pintype "passive"))
      (node (ref "VR2") (pin "5") (pinfunction "~{ON}/OFF_5") (pintype "passive"))
    )
    (net (code "70") (name "Net-(Q2-B)") (class "Default")
      (node (ref "C26") (pin "2") (pinfunction "2_2") (pintype "passive"))
      (node (ref "Q2") (pin "2") (pinfunction "B_2") (pintype "passive"))
      (node (ref "R18") (pin "2") (pinfunction "2_2") (pintype "passive"))
      (node (ref "R20") (pin "2") (pinfunction "2_2") (pintype "passive"))
    )
    (net (code "71") (name "Net-(Q2-C)") (class "Default")
      (node (ref "LS1") (pin "2") (pinfunction "2_2") (pintype "passive"))
      (node (ref "Q2") (pin "1") (pinfunction "C_1") (pintype "passive"))
    )
    (net (code "72") (name "Net-(R25-Pad1)") (class "Default")
      (node (ref "R25") (pin "1") (pinfunction "1_1") (pintype "passive"))
      (node (ref "SW2") (pin "2") (pinfunction "2_2") (pintype "passive"))
    )
    (net (code "73") (name "Net-(R26-Pad1)") (class "Default")
      (node (ref "R26") (pin "1") (pinfunction "1_1") (pintype "passive"))
      (node (ref "SW3") (pin "2") (pinfunction "2_2") (pintype "passive"))
    )
    (net (code "74") (name "Net-(R32-Pad1)") (class "Default")
      (node (ref "R32") (pin "1") (pinfunction "1_1") (pintype "passive"))
      (node (ref "SW4") (pin "2") (pinfunction "2_2") (pintype "passive"))
    )
    (net (code "75") (name "Net-(R34-Pad1)") (class "Default")
      (node (ref "R34") (pin "1") (pinfunction "1_1") (pintype "passive"))
      (node (ref "SW5") (pin "2") (pinfunction "2_2") (pintype "passive"))
    )
    (net (code "76") (name "Net-(U1-A)") (class "Default")
      (node (ref "R12") (pin "1") (pinfunction "1_1") (pintype "passive"))
      (node (ref "U1") (pin "6") (pinfunction "A_6") (pintype "passive"))
    )
    (net (code "77") (name "Net-(U1-B)") (class "Default")
      (node (ref "R10") (pin "1") (pinfunction "1_1") (pintype "passive"))
      (node (ref "U1") (pin "7") (pinfunction "B_7") (pintype "passive"))
    )
    (net (code "78") (name "Net-(VR1-FEEDBACK)") (class "Default")
      (node (ref "R5") (pin "1") (pinfunction "1_1") (pintype "passive"))
      (node (ref "R9") (pin "2") (pinfunction "2_2") (pintype "passive"))
      (node (ref "VR1") (pin "4") (pinfunction "FEEDBACK_4") (pintype "passive"))
    )
    (net (code "79") (name "Net-(VR3-FEEDBACK)") (class "Default")
      (node (ref "R19") (pin "1") (pinfunction "1_1") (pintype "passive"))
      (node (ref "R21") (pin "2") (pinfunction "2_2") (pintype "passive"))
      (node (ref "VR3") (pin "4") (pinfunction "FEEDBACK_4") (pintype "passive"))
    )
    (net (code "80") (name "Net-(VR4-FEEDBACK)") (class "Default")
      (node (ref "R27") (pin "1") (pinfunction "1_1") (pintype "passive"))
      (node (ref "R28") (pin "2") (pinfunction "2_2") (pintype "passive"))
      (node (ref "VR4") (pin "4") (pinfunction "FEEDBACK_4") (pintype "passive"))
    )
    (net (code "81") (name "Net-(VR5-FEEDBACK)") (class "Default")
      (node (ref "R39") (pin "1") (pinfunction "1_1") (pintype "passive"))
      (node (ref "R40") (pin "2") (pinfunction "2_2") (pintype "passive"))
      (node (ref "VR5") (pin "4") (pinfunction "FEEDBACK_4") (pintype "passive"))
    )
    (net (code "82") (name "VBB") (class "Default")
      (node (ref "D14") (pin "1") (pinfunction "A_1") (pintype "passive"))
      (node (ref "D17") (pin "1") (pinfunction "A_1") (pintype "passive"))
      (node (ref "D2") (pin "1") (pinfunction "A_1") (pintype "passive"))
      (node (ref "D22") (pin "1") (pinfunction "A_1") (pintype "passive"))
      (node (ref "D5") (pin "1") (pinfunction "A_1") (pintype "passive"))
      (node (ref "J2") (pin "1") (pintype "passive"))
    )
    (net (code "83") (name "VCC") (class "Default")
      (node (ref "C15") (pin "1") (pinfunction "1_1") (pintype "passive"))
      (node (ref "C16") (pin "2") (pinfunction "2_2") (pintype "passive"))
      (node (ref "C2") (pin "2") (pinfunction "2_2") (pintype "passive"))
      (node (ref "C3") (pin "2") (pinfunction "2_2") (pintype "passive"))
      (node (ref "C41") (pin "2") (pinfunction "2_2") (pintype "passive"))
      (node (ref "C42") (pin "2") (pinfunction "2_2") (pintype "passive"))
      (node (ref "C46") (pin "2") (pinfunction "2_2") (pintype "passive"))
      (node (ref "C47") (pin "2") (pinfunction "2_2") (pintype "passive"))
      (node (ref "C52") (pin "2") (pinfunction "2_2") (pintype "passive"))
      (node (ref "C53") (pin "2") (pinfunction "2_2") (pintype "passive"))
      (node (ref "C61") (pin "2") (pinfunction "2_2") (pintype "passive"))
      (node (ref "C62") (pin "2") (pinfunction "2_2") (pintype "passive"))
      (node (ref "D10") (pin "2") (pinfunction "K_2") (pintype "passive"))
      (node (ref "D27") (pin "2") (pinfunction "K_2") (pintype "passive"))
      (node (ref "H1") (pin "1") (pintype "passive"))
      (node (ref "H2") (pin "1") (pintype "passive"))
      (node (ref "H3") (pin "2") (pintype "input"))
      (node (ref "H4") (pin "2") (pintype "input"))
      (node (ref "L2") (pin "2") (pinfunction "2_2") (pintype "passive"))
      (node (ref "LS1") (pin "1") (pinfunction "1_1") (pintype "passive"))
      (node (ref "M1") (pin "21") (pinfunction "VCC_21") (pintype "passive"))
      (node (ref "M1") (pin "52") (pinfunction "VCC_52") (pintype "passive"))
      (node (ref "M1") (pin "64") (pinfunction "AVCC_64") (pintype "passive"))
      (node (ref "M2") (pin "21") (pinfunction "VCC_21") (pintype "passive"))
      (node (ref "M2") (pin "52") (pinfunction "VCC_52") (pintype "passive"))
      (node (ref "M2") (pin "64") (pinfunction "AVCC_64") (pintype "passive"))
      (node (ref "R1") (pin "1") (pinfunction "1_1") (pintype "passive"))
      (node (ref "R14") (pin "1") (pinfunction "1_1") (pintype "passive"))
      (node (ref "R2") (pin "1") (pinfunction "1_1") (pintype "passive"))
      (node (ref "R23") (pin "2") (pinfunction "2_2") (pintype "passive"))
      (node (ref "R24") (pin "2") (pinfunction "2_2") (pintype "passive"))
      (node (ref "R29") (pin "1") (pinfunction "1_1") (pintype "passive"))
      (node (ref "R30") (pin "2") (pinfunction "2_2") (pintype "passive"))
      (node (ref "R31") (pin "2") (pinfunction "2_2") (pintype "passive"))
      (node (ref "R33") (pin "1") (pinfunction "1_1") (pintype "passive"))
      (node (ref "R37") (pin "1") (pinfunction "1_1") (pintype "passive"))
      (node (ref "R4") (pin "2") (pinfunction "2_2") (pintype "passive"))
      (node (ref "R41") (pin "1") (pinfunction "1_1") (pintype "passive"))
      (node (ref "R42") (pin "1") (pinfunction "1_1") (pintype "passive"))
      (node (ref "R8") (pin "1") (pinfunction "1_1") (pintype "passive"))
      (node (ref "U1") (pin "8") (pinfunction "VCC_8") (pintype "passive"))
      (node (ref "VR2") (pin "4") (pinfunction "FEEDBACK_4") (pintype "passive"))
    )
    (net (code "84") (name "VIN") (class "Default")
      (node (ref "C1") (pin "1") (pinfunction "1_1") (pintype "passive"))
      (node (ref "C10") (pin "2") (pinfunction "2_2") (pintype "passive"))
      (node (ref "C14") (pin "2") (pinfunction "2_2") (pintype "passive"))
      (node (ref "C17") (pin "1") (pinfunction "1_1") (pintype "passive"))
      (node (ref "C18") (pin "2") (pinfunction "2_2") (pintype "passive"))
      (node (ref "C20") (pin "1") (pinfunction "1_1") (pintype "passive"))
      (node (ref "C21") (pin "2") (pinfunction "2_2") (pintype "passive"))
      (node (ref "C29") (pin "1") (pinfunction "1_1") (pintype "passive"))
      (node (ref "C30") (pin "2") (pinfunction "2_2") (pintype "passive"))
      (node (ref "C31") (pin "1") (pinfunction "1_1") (pintype "passive"))
      (node (ref "C32") (pin "2") (pinfunction "2_2") (pintype "passive"))
      (node (ref "C4") (pin "2") (pinfunction "2_2") (pintype "passive"))
      (node (ref "C7") (pin "1") (pinfunction "1_1") (pintype "passive"))
      (node (ref "D11") (pin "2") (pinfunction "K_2") (pintype "passive"))
      (node (ref "J1") (pin "4") (pintype "passive"))
      (node (ref "J5") (pin "4") (pintype "passive"))
      (node (ref "J6") (pin "4") (pintype "passive"))
      (node (ref "J8") (pin "4") (pintype "passive"))
      (node (ref "J9") (pin "4") (pintype "passive"))
      (node (ref "R7") (pin "1") (pinfunction "1_1") (pintype "passive"))
      (node (ref "T1") (pin "2") (pinfunction "2_2") (pintype "passive"))
      (node (ref "VR2") (pin "1") (pinfunction "VIN_1") (pintype "passive"))
    )
    (net (code "85") (name "VU") (class "Default")
      (node (ref "C63") (pin "2") (pinfunction "2_2") (pintype "passive"))
      (node (ref "D27") (pin "1") (pinfunction "A_1") (pintype "passive"))
      (node (ref "J12") (pin "1") (pinfunction "1_1") (pintype "passive"))
      (node (ref "M3") (pin "16") (pinfunction "VCC_16") (pintype "passive"))
    )
    (net (code "86") (name "unconnected-(H3-Pad6)") (class "Default")
      (node (ref "H3") (pin "6") (pintype "input+no_connect"))
    )
    (net (code "87") (name "unconnected-(H3-Pad7)") (class "Default")
      (node (ref "H3") (pin "7") (pintype "input+no_connect"))
    )
    (net (code "88") (name "unconnected-(H4-Pad6)") (class "Default")
      (node (ref "H4") (pin "6") (pintype "input+no_connect"))
    )
    (net (code "89") (name "unconnected-(H4-Pad7)") (class "Default")
      (node (ref "H4") (pin "7") (pintype "input+no_connect"))
    )
    (net (code "90") (name "unconnected-(M1-AREFF-Pad62)") (class "Default")
      (node (ref "M1") (pin "62") (pinfunction "AREFF_62") (pintype "passive+no_connect"))
    )
    (net (code "91") (name "unconnected-(M1-PA0-Pad51)") (class "Default")
      (node (ref "M1") (pin "51") (pinfunction "PA0_51") (pintype "passive"))
    )
    (net (code "92") (name "unconnected-(M1-PA1-Pad50)") (class "Default")
      (node (ref "M1") (pin "50") (pinfunction "PA1_50") (pintype "passive"))
    )
    (net (code "93") (name "unconnected-(M1-PA2-Pad49)") (class "Default")
      (node (ref "M1") (pin "49") (pinfunction "PA2_49") (pintype "passive"))
    )
    (net (code "94") (name "unconnected-(M1-PA3-Pad48)") (class "Default")
      (node (ref "M1") (pin "48") (pinfunction "PA3_48") (pintype "passive"))
    )
    (net (code "95") (name "unconnected-(M1-PA4-Pad47)") (class "Default")
      (node (ref "M1") (pin "47") (pinfunction "PA4_47") (pintype "passive"))
    )
    (net (code "96") (name "unconnected-(M1-PA5-Pad46)") (class "Default")
      (node (ref "M1") (pin "46") (pinfunction "PA5_46") (pintype "passive"))
    )
    (net (code "97") (name "unconnected-(M1-PA6-Pad45)") (class "Default")
      (node (ref "M1") (pin "45") (pinfunction "PA6_45") (pintype "passive"))
    )
    (net (code "98") (name "unconnected-(M1-PA7-Pad44)") (class "Default")
      (node (ref "M1") (pin "44") (pinfunction "PA7_44") (pintype "passive"))
    )
    (net (code "99") (name "unconnected-(M1-PB0-Pad10)") (class "Default")
      (node (ref "M1") (pin "10") (pinfunction "PB0_10") (pintype "passive"))
    )
    (net (code "100") (name "unconnected-(M1-PB2{slash}MOSI-Pad12)") (class "Default")
      (node (ref "M1") (pin "12") (pinfunction "PB2/MOSI_12") (pintype "passive"))
    )
    (net (code "101") (name "unconnected-(M1-PB3{slash}MISO-Pad13)") (class "Default")
      (node (ref "M1") (pin "13") (pinfunction "PB3/MISO_13") (pintype "passive"))
    )
    (net (code "102") (name "unconnected-(M1-PB4-Pad14)") (class "Default")
      (node (ref "M1") (pin "14") (pinfunction "PB4_14") (pintype "passive"))
    )
    (net (code "103") (name "unconnected-(M1-PB5-Pad15)") (class "Default")
      (node (ref "M1") (pin "15") (pinfunction "PB5_15") (pintype "passive"))
    )
    (net (code "104") (name "unconnected-(M1-PB6-Pad16)") (class "Default")
      (node (ref "M1") (pin "16") (pinfunction "PB6_16") (pintype "passive"))
    )
    (net (code "105") (name "unconnected-(M1-PB7-Pad17)") (class "Default")
      (node (ref "M1") (pin "17") (pinfunction "PB7_17") (pintype "passive"))
    )
    (net (code "106") (name "unconnected-(M1-PC0-Pad35)") (class "Default")
      (node (ref "M1") (pin "35") (pinfunction "PC0_35") (pintype "passive"))
    )
    (net (code "107") (name "unconnected-(M1-PC1-Pad36)") (class "Default")
      (node (ref "M1") (pin "36") (pinfunction "PC1_36") (pintype "passive"))
    )
    (net (code "108") (name "unconnected-(M1-PC2-Pad37)") (class "Default")
      (node (ref "M1") (pin "37") (pinfunction "PC2_37") (pintype "passive"))
    )
    (net (code "109") (name "unconnected-(M1-PC3-Pad38)") (class "Default")
      (node (ref "M1") (pin "38") (pinfunction "PC3_38") (pintype "passive"))
    )
    (net (code "110") (name "unconnected-(M1-PC4-Pad39)") (class "Default")
      (node (ref "M1") (pin "39") (pinfunction "PC4_39") (pintype "passive"))
    )
    (net (code "111") (name "unconnected-(M1-PC5-Pad40)") (class "Default")
      (node (ref "M1") (pin "40") (pinfunction "PC5_40") (pintype "passive"))
    )
    (net (code "112") (name "unconnected-(M1-PC6-Pad41)") (class "Default")
      (node (ref "M1") (pin "41") (pinfunction "PC6_41") (pintype "passive"))
    )
    (net (code "113") (name "unconnected-(M1-PC7-Pad42)") (class "Default")
      (node (ref "M1") (pin "42") (pinfunction "PC7_42") (pintype "passive"))
    )
    (net (code "114") (name "unconnected-(M1-PD0-Pad25)") (class "Default")
      (node (ref "M1") (pin "25") (pinfunction "PD0_25") (pintype "passive"))
    )
    (net (code "115") (name "unconnected-(M1-PD1-Pad26)") (class "Default")
      (node (ref "M1") (pin "26") (pinfunction "PD1_26") (pintype "passive"))
    )
    (net (code "116") (name "unconnected-(M1-PD5-Pad30)") (class "Default")
      (node (ref "M1") (pin "30") (pinfunction "PD5_30") (pintype "passive"))
    )
    (net (code "117") (name "unconnected-(M1-PD6-Pad31)") (class "Default")
      (node (ref "M1") (pin "31") (pinfunction "PD6_31") (pintype "passive"))
    )
    (net (code "118") (name "unconnected-(M1-PD7-Pad32)") (class "Default")
      (node (ref "M1") (pin "32") (pinfunction "PD7_32") (pintype "passive"))
    )
    (net (code "119") (name "unconnected-(M1-PE2-Pad4)") (class "Default")
      (node (ref "M1") (pin "4") (pinfunction "PE2_4") (pintype "passive"))
    )
    (net (code "120") (name "unconnected-(M1-PE3-Pad5)") (class "Default")
      (node (ref "M1") (pin "5") (pinfunction "PE3_5") (pintype "passive"))
    )
    (net (code "121") (name "unconnected-(M1-PE4-Pad6)") (class "Default")
      (node (ref "M1") (pin "6") (pinfunction "PE4_6") (pintype "passive"))
    )
    (net (code "122") (name "unconnected-(M1-PE5-Pad7)") (class "Default")
      (node (ref "M1") (pin "7") (pinfunction "PE5_7") (pintype "passive"))
    )
    (net (code "123") (name "unconnected-(M1-PE6-Pad8)") (class "Default")
      (node (ref "M1") (pin "8") (pinfunction "PE6_8") (pintype "passive"))
    )
    (net (code "124") (name "unconnected-(M1-PE7-Pad9)") (class "Default")
      (node (ref "M1") (pin "9") (pinfunction "PE7_9") (pintype "passive"))
    )
    (net (code "125") (name "unconnected-(M1-PEN-Pad1)") (class "Default")
      (node (ref "M1") (pin "1") (pinfunction "PEN_1") (pintype "passive+no_connect"))
    )
    (net (code "126") (name "unconnected-(M1-PF0{slash}ADC0-Pad61)") (class "Default")
      (node (ref "M1") (pin "61") (pinfunction "PF0/ADC0_61") (pintype "passive"))
    )
    (net (code "127") (name "unconnected-(M1-PF1{slash}ADC1-Pad60)") (class "Default")
      (node (ref "M1") (pin "60") (pinfunction "PF1/ADC1_60") (pintype "passive"))
    )
    (net (code "128") (name "unconnected-(M1-PF2{slash}ADC2-Pad59)") (class "Default")
      (node (ref "M1") (pin "59") (pinfunction "PF2/ADC2_59") (pintype "passive"))
    )
    (net (code "129") (name "unconnected-(M1-PF3{slash}{slash}ADC3-Pad58)") (class "Default")
      (node (ref "M1") (pin "58") (pinfunction "PF3//ADC3_58") (pintype "passive"))
    )
    (net (code "130") (name "unconnected-(M1-PF4{slash}ADC4-Pad57)") (class "Default")
      (node (ref "M1") (pin "57") (pinfunction "PF4/ADC4_57") (pintype "passive"))
    )
    (net (code "131") (name "unconnected-(M1-PF5{slash}ADC5-Pad56)") (class "Default")
      (node (ref "M1") (pin "56") (pinfunction "PF5/ADC5_56") (pintype "passive"))
    )
    (net (code "132") (name "unconnected-(M1-PF6{slash}ADC6-Pad55)") (class "Default")
      (node (ref "M1") (pin "55") (pinfunction "PF6/ADC6_55") (pintype "passive"))
    )
    (net (code "133") (name "unconnected-(M1-PF7{slash}ADC7-Pad54)") (class "Default")
      (node (ref "M1") (pin "54") (pinfunction "PF7/ADC7_54") (pintype "passive"))
    )
    (net (code "134") (name "unconnected-(M1-PG0-Pad33)") (class "Default")
      (node (ref "M1") (pin "33") (pinfunction "PG0_33") (pintype "passive"))
    )
    (net (code "135") (name "unconnected-(M1-PG1-Pad34)") (class "Default")
      (node (ref "M1") (pin "34") (pinfunction "PG1_34") (pintype "passive"))
    )
    (net (code "136") (name "unconnected-(M1-PG2-Pad43)") (class "Default")
      (node (ref "M1") (pin "43") (pinfunction "PG2_43") (pintype "passive"))
    )
    (net (code "137") (name "unconnected-(M1-PG3-Pad18)") (class "Default")
      (node (ref "M1") (pin "18") (pinfunction "PG3_18") (pintype "passive"))
    )
    (net (code "138") (name "unconnected-(M1-PG4-Pad19)") (class "Default")
      (node (ref "M1") (pin "19") (pinfunction "PG4_19") (pintype "passive"))
    )
    (net (code "139") (name "unconnected-(M2-AREFF-Pad62)") (class "Default")
      (node (ref "M2") (pin "62") (pinfunction "AREFF_62") (pintype "passive+no_connect"))
    )
    (net (code "140") (name "unconnected-(M2-PA0-Pad51)") (class "Default")
      (node (ref "M2") (pin "51") (pinfunction "PA0_51") (pintype "passive"))
    )
    (net (code "141") (name "unconnected-(M2-PA1-Pad50)") (class "Default")
      (node (ref "M2") (pin "50") (pinfunction "PA1_50") (pintype "passive"))
    )
    (net (code "142") (name "unconnected-(M2-PA2-Pad49)") (class "Default")
      (node (ref "M2") (pin "49") (pinfunction "PA2_49") (pintype "passive+no_connect"))
    )
    (net (code "143") (name "unconnected-(M2-PA4-Pad47)") (class "Default")
      (node (ref "M2") (pin "47") (pinfunction "PA4_47") (pintype "passive"))
    )
    (net (code "144") (name "unconnected-(M2-PA5-Pad46)") (class "Default")
      (node (ref "M2") (pin "46") (pinfunction "PA5_46") (pintype "passive"))
    )
    (net (code "145") (name "unconnected-(M2-PA6-Pad45)") (class "Default")
      (node (ref "M2") (pin "45") (pinfunction "PA6_45") (pintype "passive"))
    )
    (net (code "146") (name "unconnected-(M2-PA7-Pad44)") (class "Default")
      (node (ref "M2") (pin "44") (pinfunction "PA7_44") (pintype "passive"))
    )
    (net (code "147") (name "unconnected-(M2-PB0-Pad10)") (class "Default")
      (node (ref "M2") (pin "10") (pinfunction "PB0_10") (pintype "passive"))
    )
    (net (code "148") (name "unconnected-(M2-PB2{slash}MOSI-Pad12)") (class "Default")
      (node (ref "M2") (pin "12") (pinfunction "PB2/MOSI_12") (pintype "passive"))
    )
    (net (code "149") (name "unconnected-(M2-PB3{slash}MISO-Pad13)") (class "Default")
      (node (ref "M2") (pin "13") (pinfunction "PB3/MISO_13") (pintype "passive"))
    )
    (net (code "150") (name "unconnected-(M2-PC0-Pad35)") (class "Default")
      (node (ref "M2") (pin "35") (pinfunction "PC0_35") (pintype "passive+no_connect"))
    )
    (net (code "151") (name "unconnected-(M2-PC1-Pad36)") (class "Default")
      (node (ref "M2") (pin "36") (pinfunction "PC1_36") (pintype "passive+no_connect"))
    )
    (net (code "152") (name "unconnected-(M2-PC2-Pad37)") (class "Default")
      (node (ref "M2") (pin "37") (pinfunction "PC2_37") (pintype "passive+no_connect"))
    )
    (net (code "153") (name "unconnected-(M2-PC3-Pad38)") (class "Default")
      (node (ref "M2") (pin "38") (pinfunction "PC3_38") (pintype "passive+no_connect"))
    )
    (net (code "154") (name "unconnected-(M2-PC4-Pad39)") (class "Default")
      (node (ref "M2") (pin "39") (pinfunction "PC4_39") (pintype "passive+no_connect"))
    )
    (net (code "155") (name "unconnected-(M2-PC5-Pad40)") (class "Default")
      (node (ref "M2") (pin "40") (pinfunction "PC5_40") (pintype "passive+no_connect"))
    )
    (net (code "156") (name "unconnected-(M2-PC6-Pad41)") (class "Default")
      (node (ref "M2") (pin "41") (pinfunction "PC6_41") (pintype "passive+no_connect"))
    )
    (net (code "157") (name "unconnected-(M2-PC7-Pad42)") (class "Default")
      (node (ref "M2") (pin "42") (pinfunction "PC7_42") (pintype "passive+no_connect"))
    )
    (net (code "158") (name "unconnected-(M2-PD0-Pad25)") (class "Default")
      (node (ref "M2") (pin "25") (pinfunction "PD0_25") (pintype "passive+no_connect"))
    )
    (net (code "159") (name "unconnected-(M2-PD1-Pad26)") (class "Default")
      (node (ref "M2") (pin "26") (pinfunction "PD1_26") (pintype "passive+no_connect"))
    )
    (net (code "160") (name "unconnected-(M2-PD4-Pad29)") (class "Default")
      (node (ref "M2") (pin "29") (pinfunction "PD4_29") (pintype "passive+no_connect"))
    )
    (net (code "161") (name "unconnected-(M2-PD5-Pad30)") (class "Default")
      (node (ref "M2") (pin "30") (pinfunction "PD5_30") (pintype "passive+no_connect"))
    )
    (net (code "162") (name "unconnected-(M2-PD6-Pad31)") (class "Default")
      (node (ref "M2") (pin "31") (pinfunction "PD6_31") (pintype "passive+no_connect"))
    )
    (net (code "163") (name "unconnected-(M2-PD7-Pad32)") (class "Default")
      (node (ref "M2") (pin "32") (pinfunction "PD7_32") (pintype "passive+no_connect"))
    )
    (net (code "164") (name "unconnected-(M2-PE6-Pad8)") (class "Default")
      (node (ref "M2") (pin "8") (pinfunction "PE6_8") (pintype "passive"))
    )
    (net (code "165") (name "unconnected-(M2-PE7-Pad9)") (class "Default")
      (node (ref "M2") (pin "9") (pinfunction "PE7_9") (pintype "passive"))
    )
    (net (code "166") (name "unconnected-(M2-PEN-Pad1)") (class "Default")
      (node (ref "M2") (pin "1") (pinfunction "PEN_1") (pintype "passive+no_connect"))
    )
    (net (code "167") (name "unconnected-(M2-PF0{slash}ADC0-Pad61)") (class "Default")
      (node (ref "M2") (pin "61") (pinfunction "PF0/ADC0_61") (pintype "passive"))
    )
    (net (code "168") (name "unconnected-(M2-PF1{slash}ADC1-Pad60)") (class "Default")
      (node (ref "M2") (pin "60") (pinfunction "PF1/ADC1_60") (pintype "passive"))
    )
    (net (code "169") (name "unconnected-(M2-PF2{slash}ADC2-Pad59)") (class "Default")
      (node (ref "M2") (pin "59") (pinfunction "PF2/ADC2_59") (pintype "passive"))
    )
    (net (code "170") (name "unconnected-(M2-PF3{slash}{slash}ADC3-Pad58)") (class "Default")
      (node (ref "M2") (pin "58") (pinfunction "PF3//ADC3_58") (pintype "passive"))
    )
    (net (code "171") (name "unconnected-(M2-PF4{slash}ADC4-Pad57)") (class "Default")
      (node (ref "M2") (pin "57") (pinfunction "PF4/ADC4_57") (pintype "passive"))
    )
    (net (code "172") (name "unconnected-(M2-PF5{slash}ADC5-Pad56)") (class "Default")
      (node (ref "M2") (pin "56") (pinfunction "PF5/ADC5_56") (pintype "passive"))
    )
    (net (code "173") (name "unconnected-(M2-PF6{slash}ADC6-Pad55)") (class "Default")
      (node (ref "M2") (pin "55") (pinfunction "PF6/ADC6_55") (pintype "passive"))
    )
    (net (code "174") (name "unconnected-(M2-PF7{slash}ADC7-Pad54)") (class "Default")
      (node (ref "M2") (pin "54") (pinfunction "PF7/ADC7_54") (pintype "passive"))
    )
    (net (code "175") (name "unconnected-(M2-PG0-Pad33)") (class "Default")
      (node (ref "M2") (pin "33") (pinfunction "PG0_33") (pintype "passive+no_connect"))
    )
    (net (code "176") (name "unconnected-(M2-PG1-Pad34)") (class "Default")
      (node (ref "M2") (pin "34") (pinfunction "PG1_34") (pintype "passive+no_connect"))
    )
    (net (code "177") (name "unconnected-(M2-PG2-Pad43)") (class "Default")
      (node (ref "M2") (pin "43") (pinfunction "PG2_43") (pintype "passive+no_connect"))
    )
    (net (code "178") (name "unconnected-(M2-PG3-Pad18)") (class "Default")
      (node (ref "M2") (pin "18") (pinfunction "PG3_18") (pintype "passive"))
    )
    (net (code "179") (name "unconnected-(M2-PG4-Pad19)") (class "Default")
      (node (ref "M2") (pin "19") (pinfunction "PG4_19") (pintype "passive"))
    )
    (net (code "180") (name "unconnected-(M3-CTS-Pad9)") (class "Default")
      (node (ref "M3") (pin "9") (pinfunction "CTS_9") (pintype "passive+no_connect"))
    )
    (net (code "181") (name "unconnected-(M3-DCD-Pad12)") (class "Default")
      (node (ref "M3") (pin "12") (pinfunction "DCD_12") (pintype "passive+no_connect"))
    )
    (net (code "182") (name "unconnected-(M3-DSR-Pad10)") (class "Default")
      (node (ref "M3") (pin "10") (pinfunction "DSR_10") (pintype "passive+no_connect"))
    )
    (net (code "183") (name "unconnected-(M3-DTR-Pad13)") (class "Default")
      (node (ref "M3") (pin "13") (pinfunction "DTR_13") (pintype "passive+no_connect"))
    )
    (net (code "184") (name "unconnected-(M3-RI-Pad11)") (class "Default")
      (node (ref "M3") (pin "11") (pinfunction "RI_11") (pintype "passive+no_connect"))
    )
    (net (code "185") (name "unconnected-(M3-RS232-Pad15)") (class "Default")
      (node (ref "M3") (pin "15") (pinfunction "RS232_15") (pintype "passive+no_connect"))
    )
    (net (code "186") (name "unconnected-(M3-RTS-Pad14)") (class "Default")
      (node (ref "M3") (pin "14") (pinfunction "RTS_14") (pintype "passive+no_connect"))
    )
  )
)
